# shelves_v60.net
KiCad netlist of a schematic drawn in EAGLE
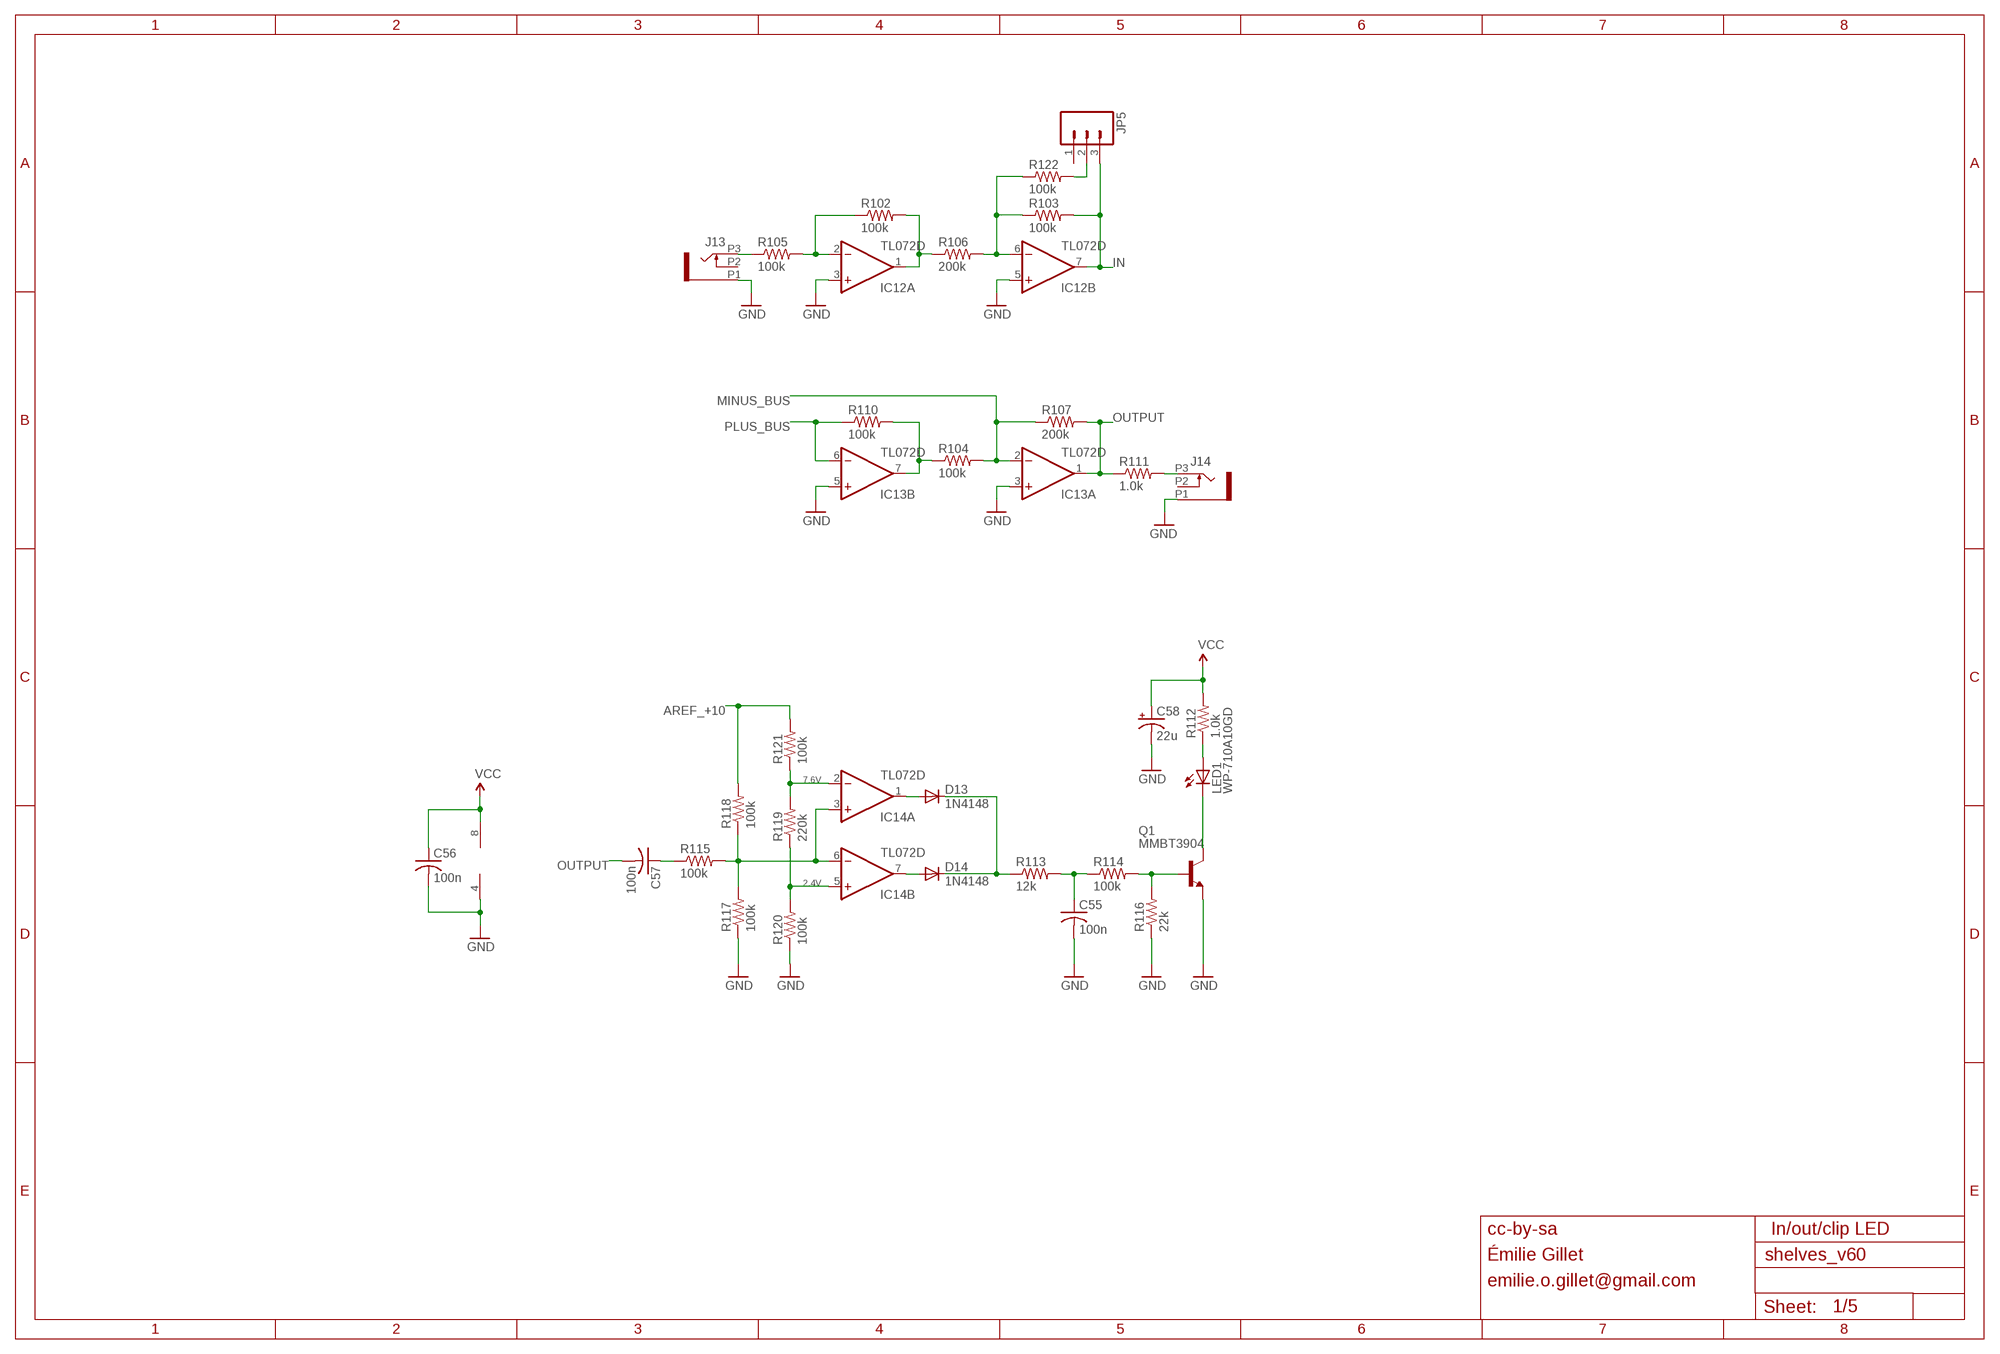
[diagram p0: schematic, sheet 1]
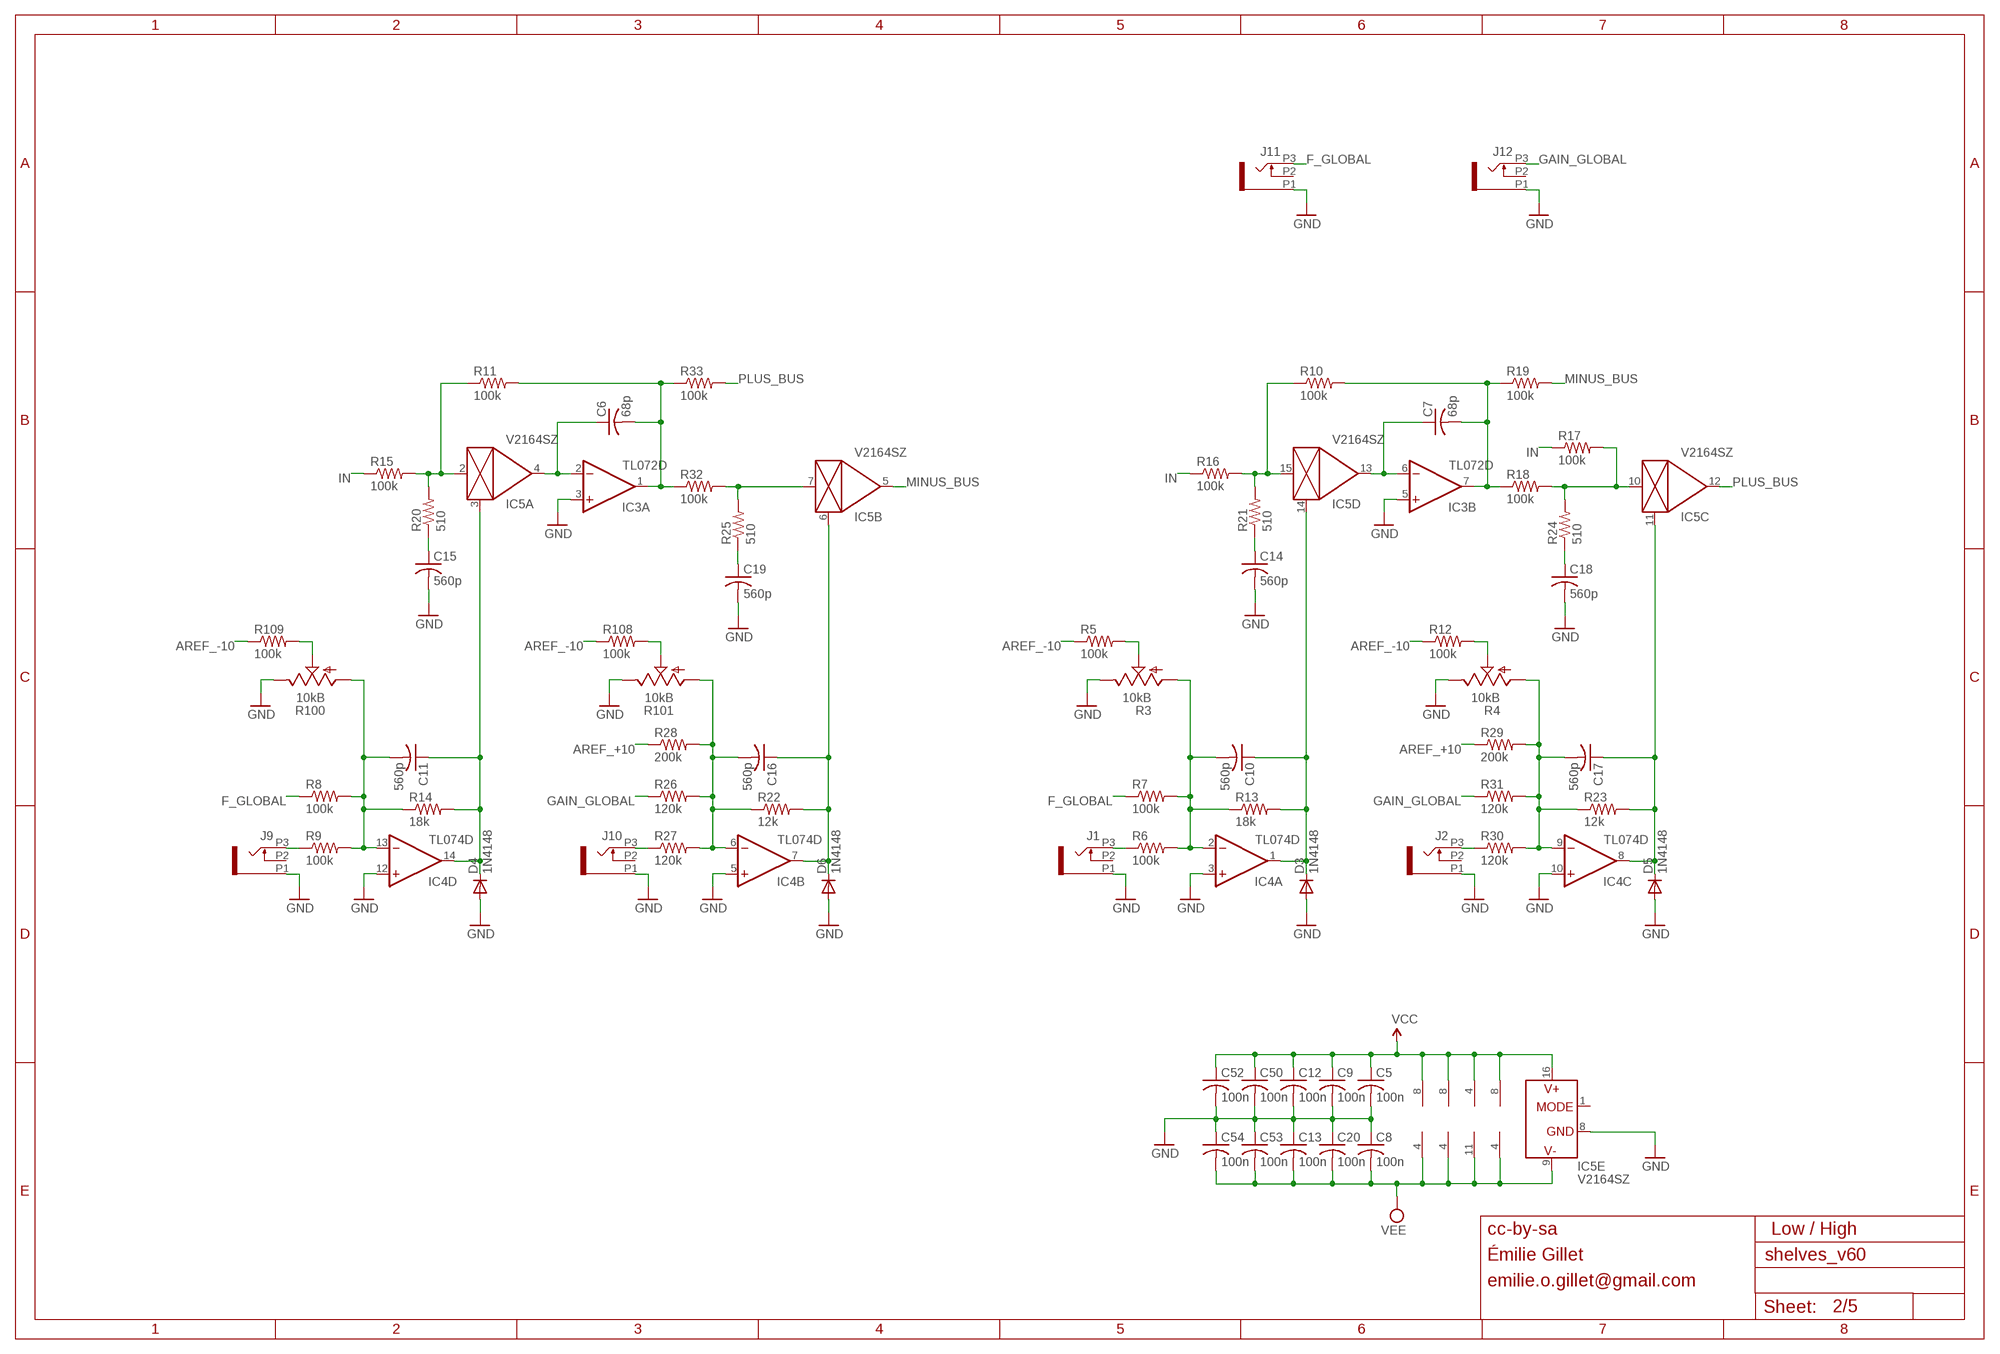
[diagram p1: schematic, sheet 2]
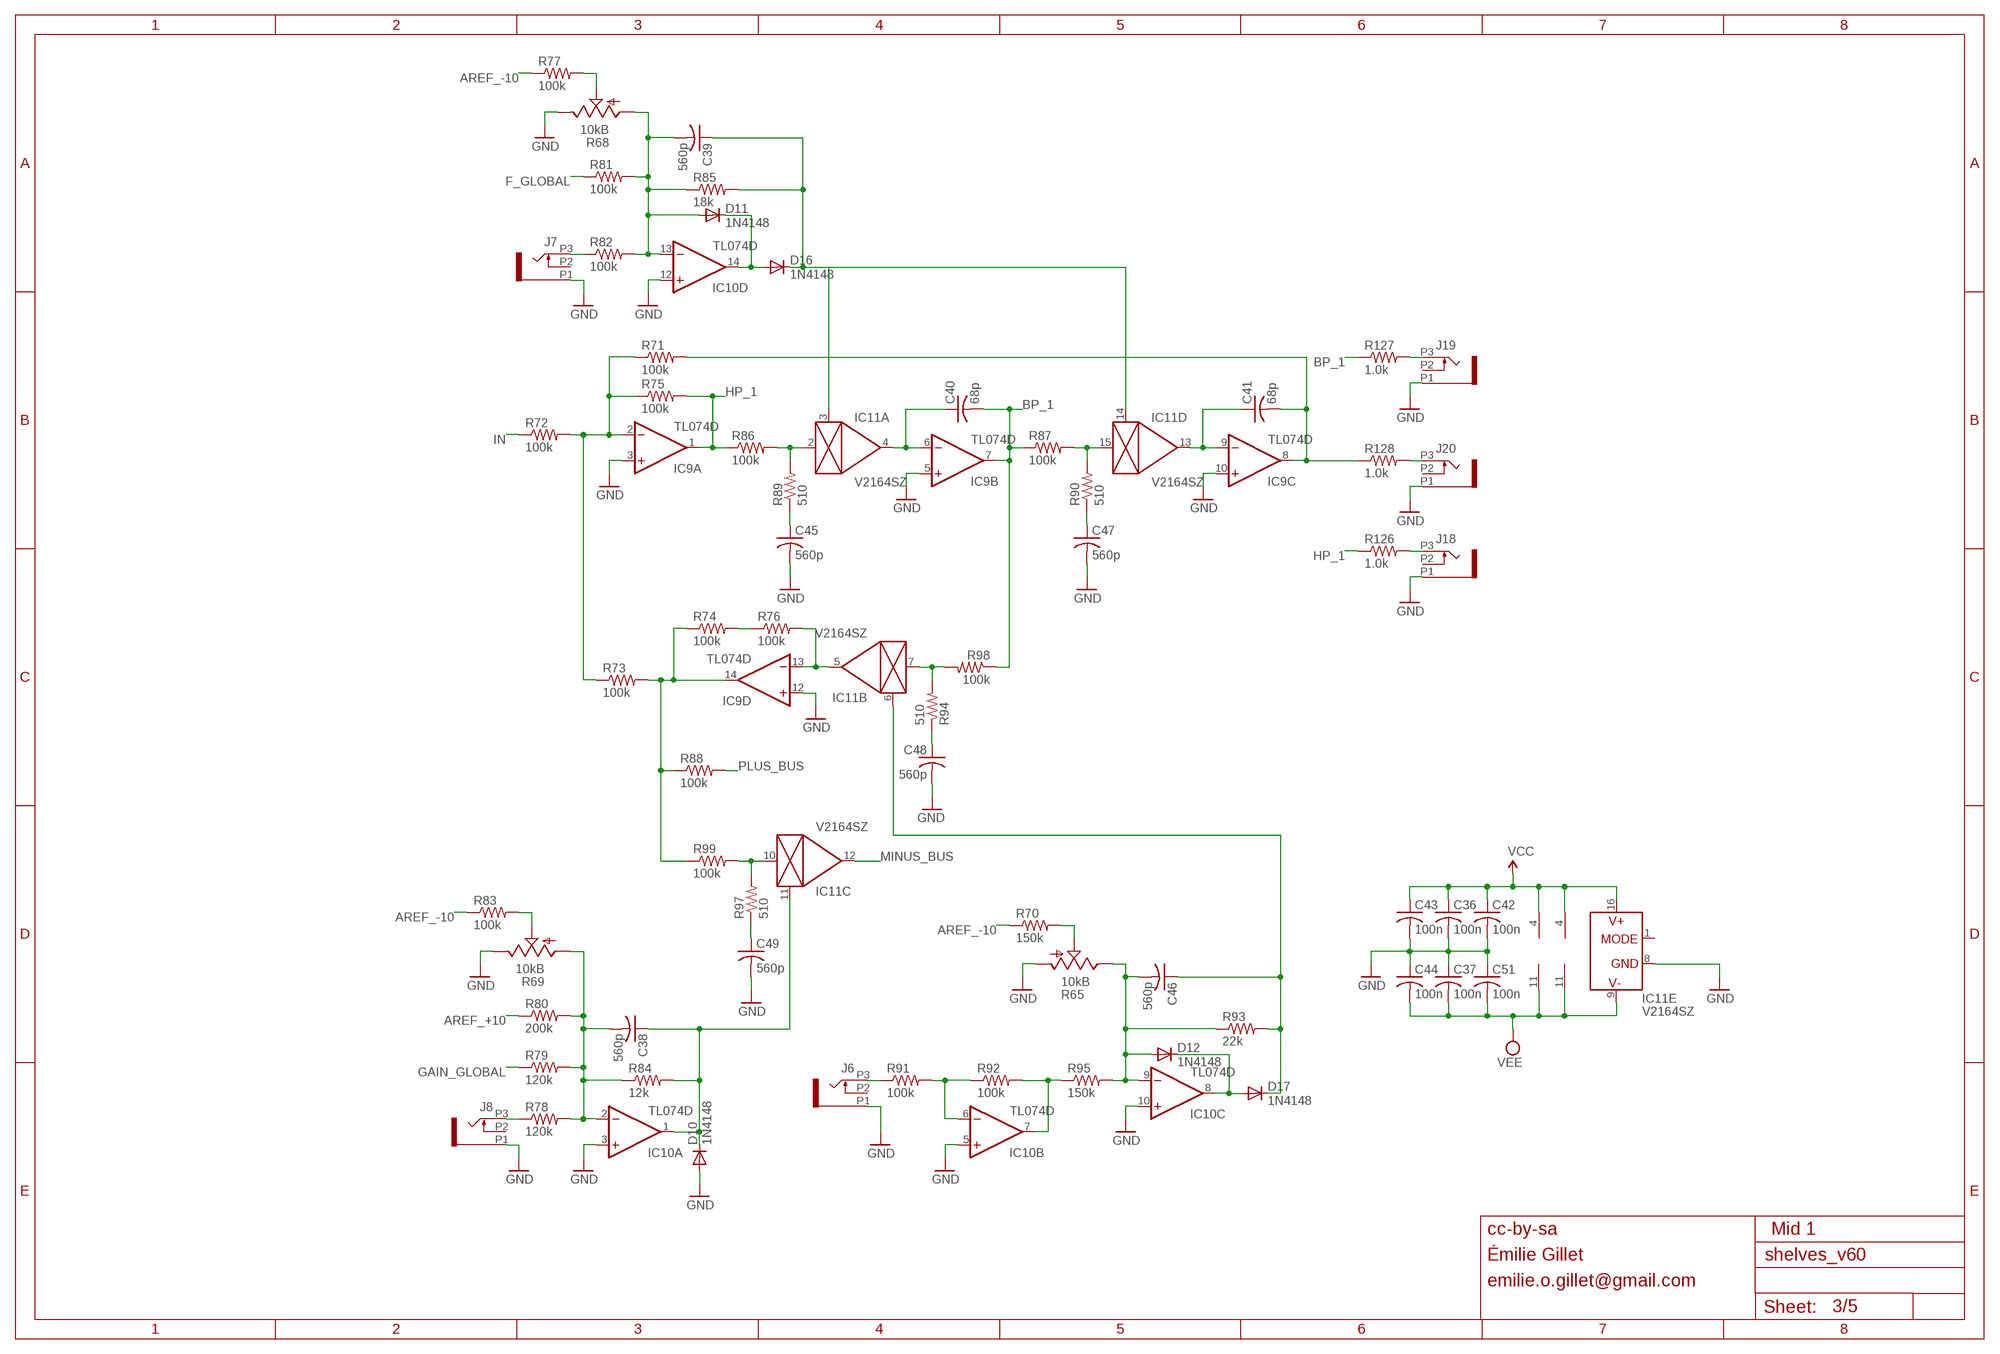
[diagram p2: schematic, sheet 3]
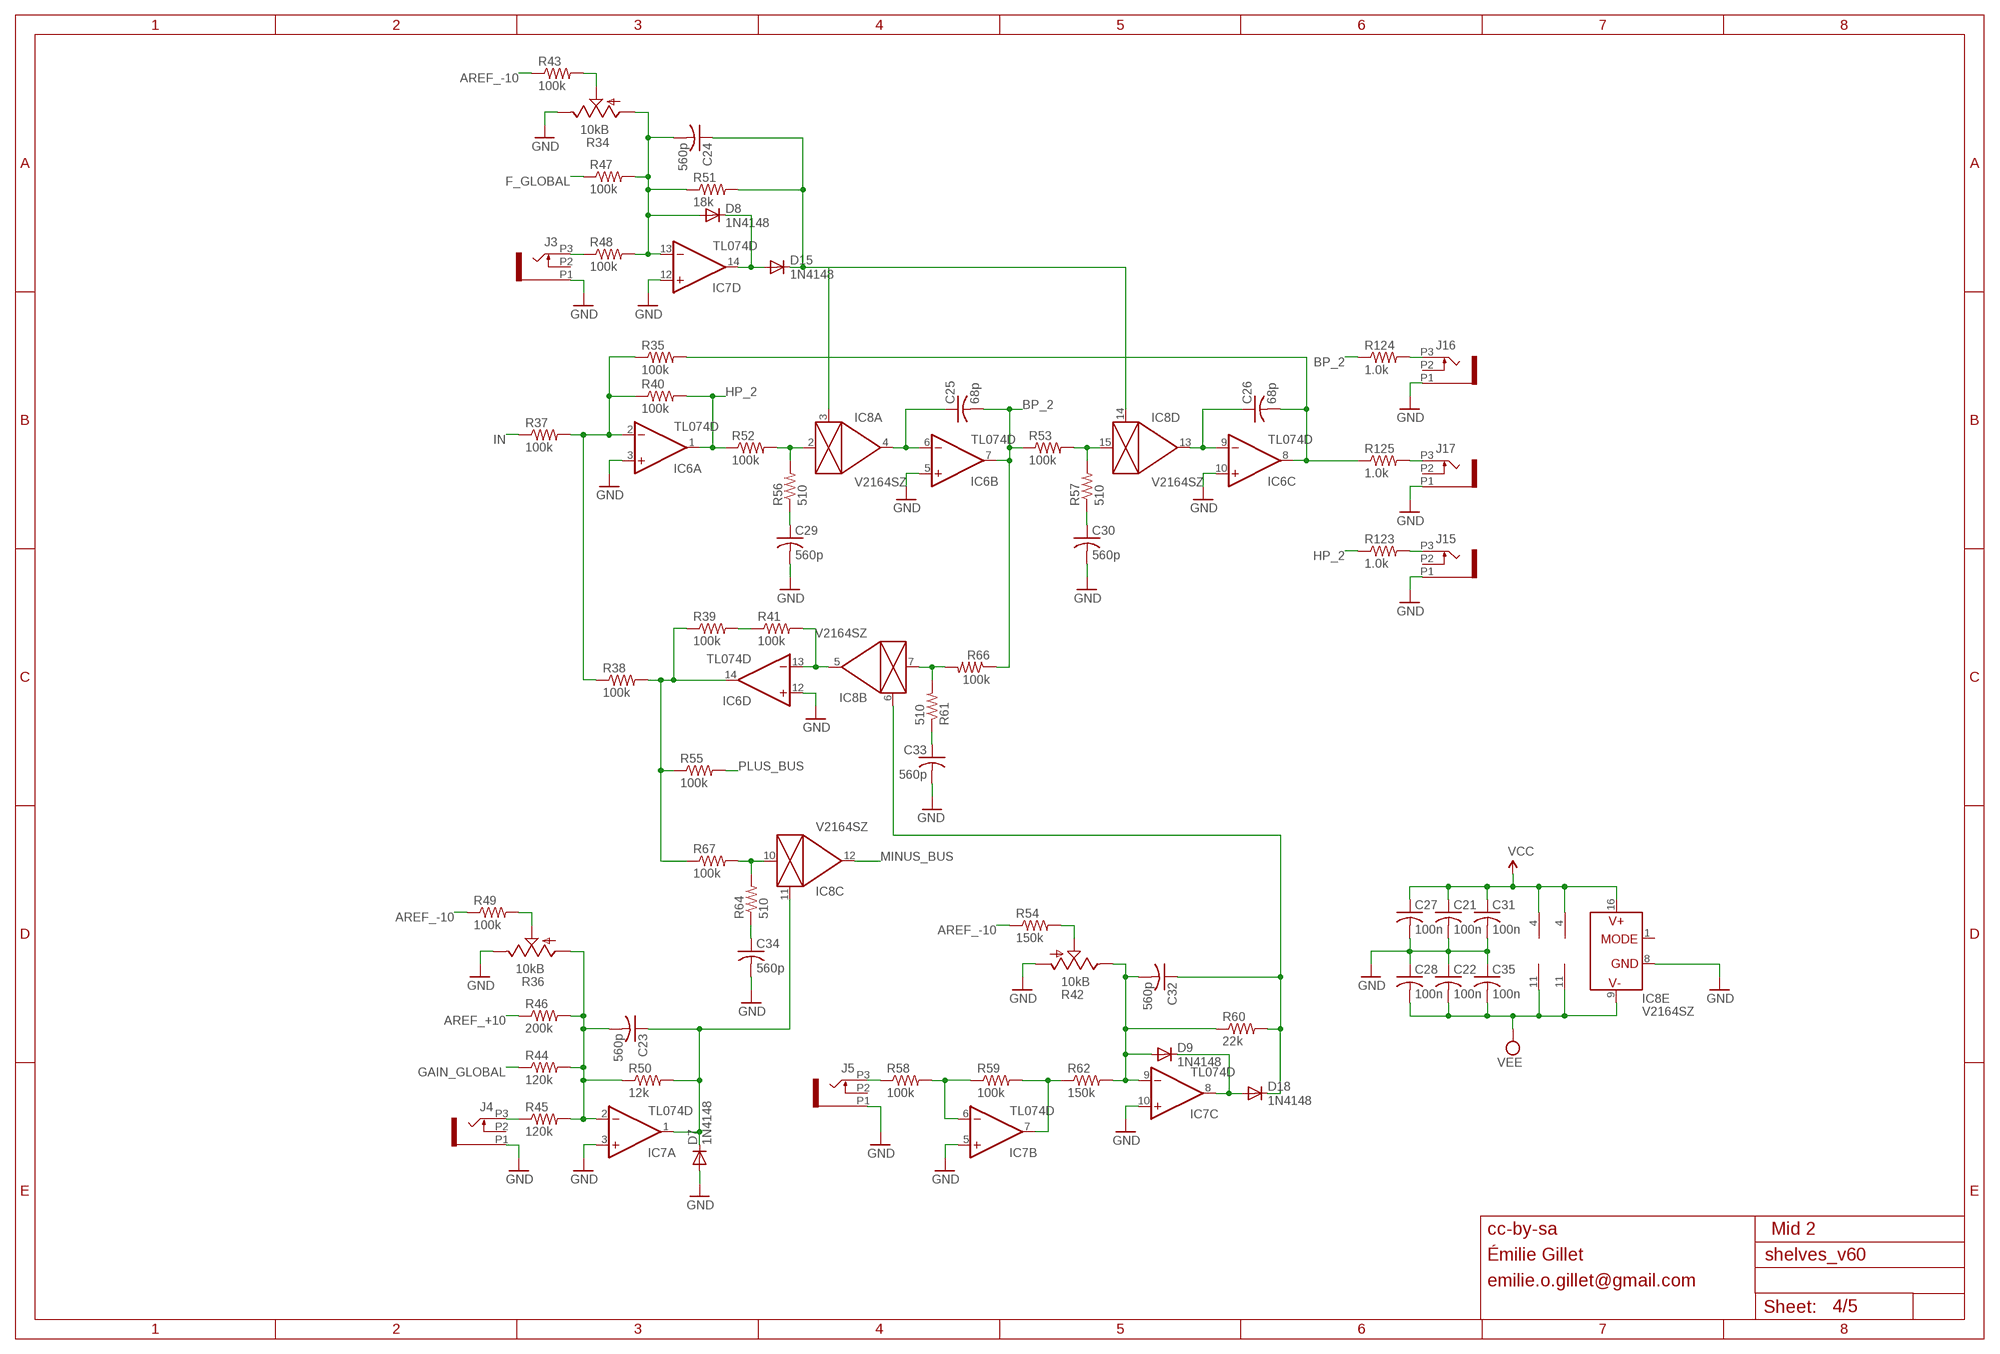
[diagram p3: schematic, sheet 4]
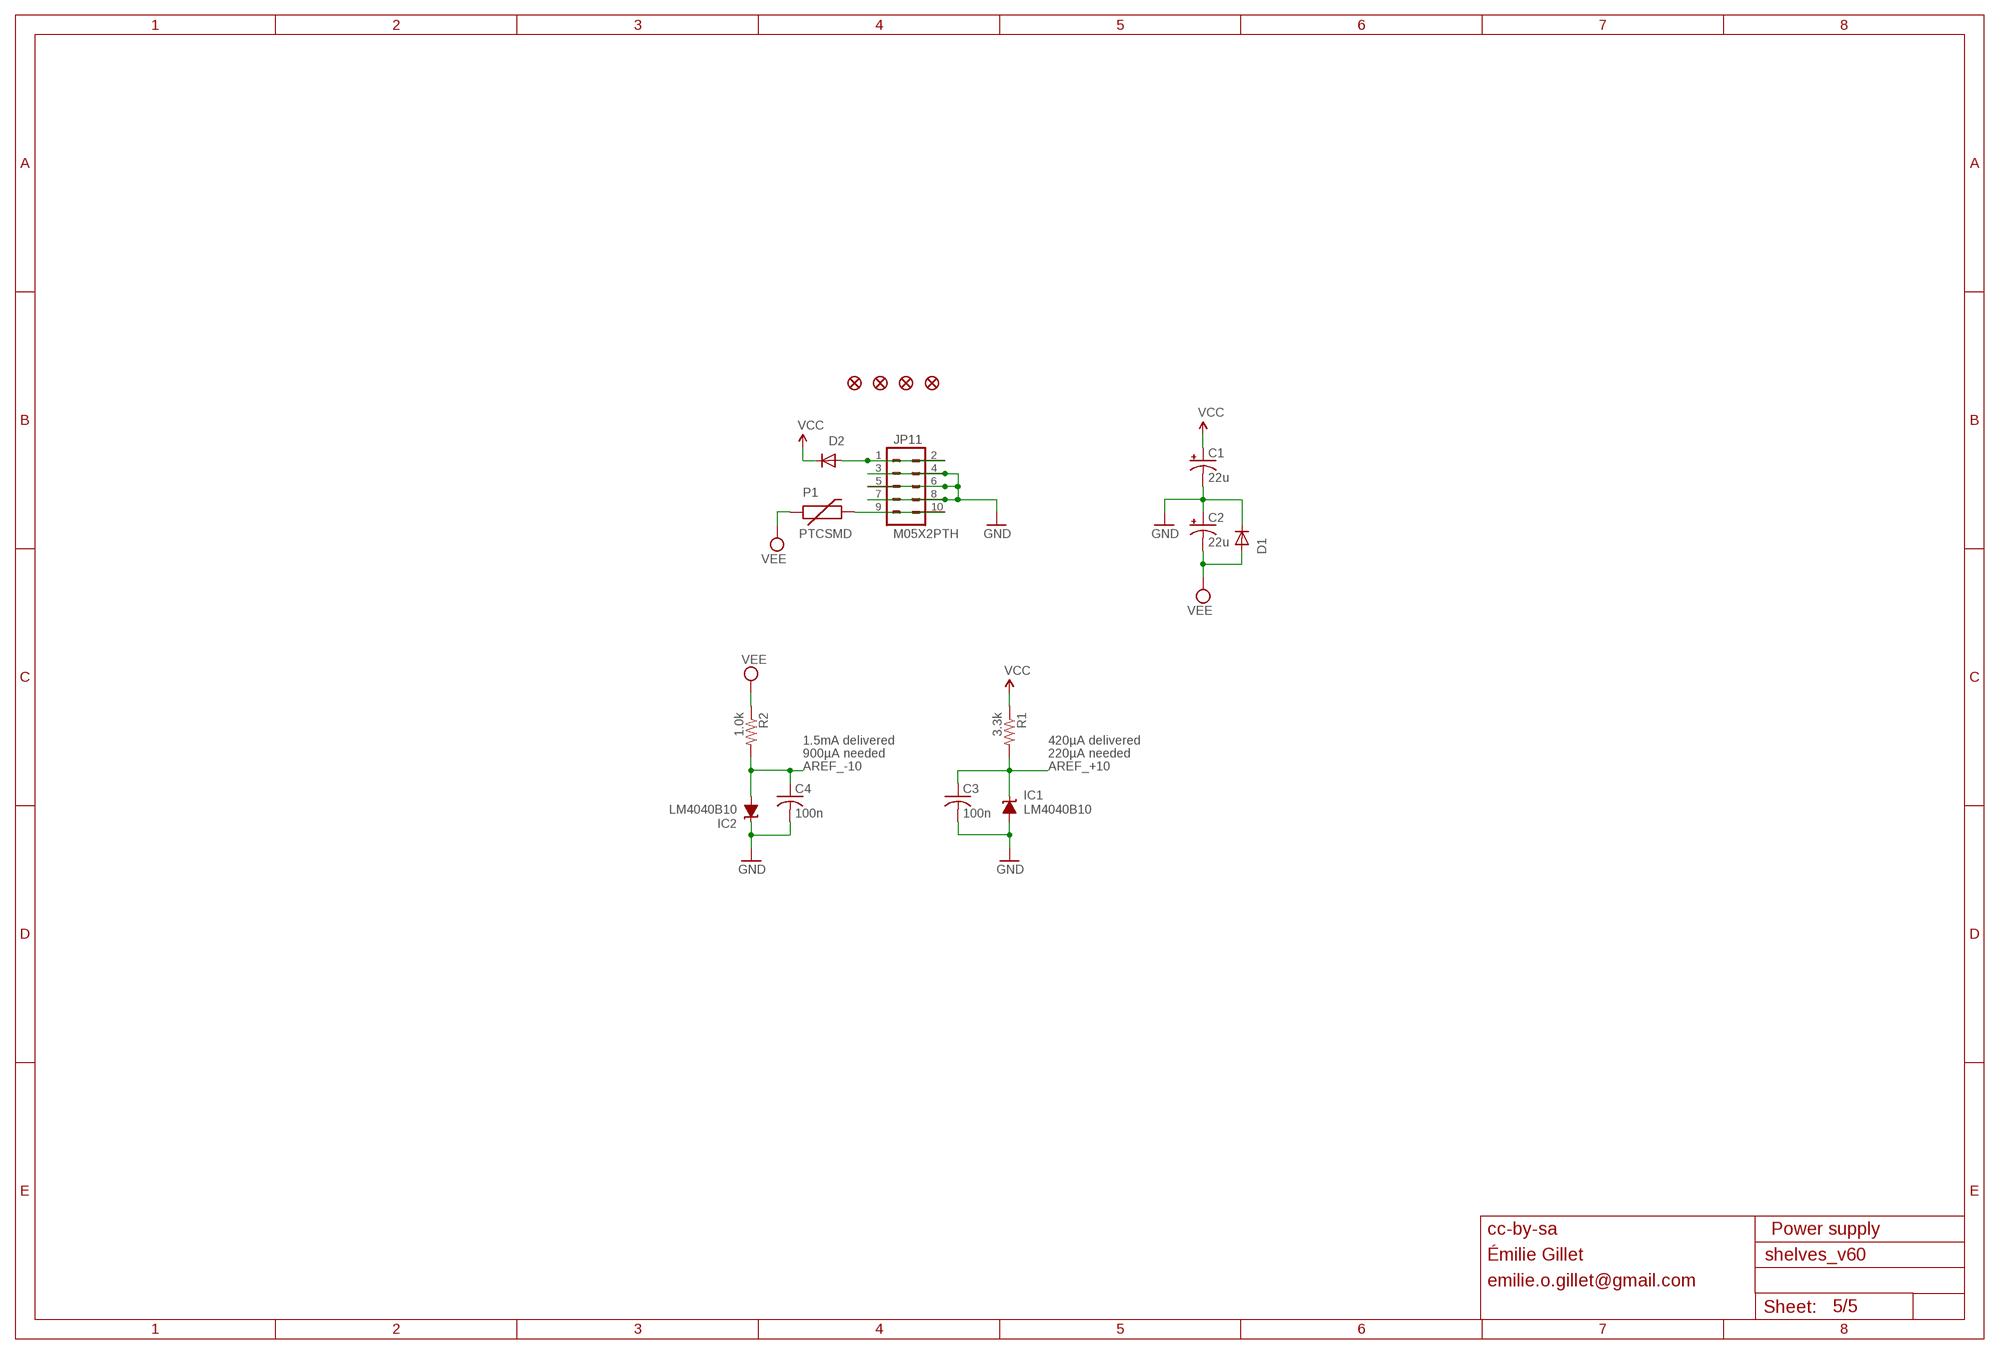
[diagram p4: schematic, sheet 5]

(export (version "E")
  (design (tool "Eeschema 10.0.6"))
  (components
    (comp (ref "C21")
      (value "100n")
      (footprint "eagle-import:C0603")
      (libsource (lib "eagle-import") (part "C-USC0603"))
    )
    (comp (ref "C22")
      (value "100n")
      (footprint "eagle-import:C0603")
      (libsource (lib "eagle-import") (part "C-USC0603"))
    )
    (comp (ref "C23")
      (value "560p")
      (footprint "eagle-import:C0603")
      (libsource (lib "eagle-import") (part "C-USC0603"))
    )
    (comp (ref "C24")
      (value "560p")
      (footprint "eagle-import:C0603")
      (libsource (lib "eagle-import") (part "C-USC0603"))
    )
    (comp (ref "C25")
      (value "68p")
      (footprint "eagle-import:C0603")
      (libsource (lib "eagle-import") (part "C-USC0603"))
    )
    (comp (ref "C26")
      (value "68p")
      (footprint "eagle-import:C0603")
      (libsource (lib "eagle-import") (part "C-USC0603"))
    )
    (comp (ref "C27")
      (value "100n")
      (footprint "eagle-import:C0603")
      (libsource (lib "eagle-import") (part "C-USC0603"))
    )
    (comp (ref "C28")
      (value "100n")
      (footprint "eagle-import:C0603")
      (libsource (lib "eagle-import") (part "C-USC0603"))
    )
    (comp (ref "C29")
      (value "560p")
      (footprint "eagle-import:C0603")
      (libsource (lib "eagle-import") (part "C-USC0603"))
    )
    (comp (ref "C30")
      (value "560p")
      (footprint "eagle-import:C0603")
      (libsource (lib "eagle-import") (part "C-USC0603"))
    )
    (comp (ref "C31")
      (value "100n")
      (footprint "eagle-import:C0603")
      (libsource (lib "eagle-import") (part "C-USC0603"))
    )
    (comp (ref "C32")
      (value "560p")
      (footprint "eagle-import:C0603")
      (libsource (lib "eagle-import") (part "C-USC0603"))
    )
    (comp (ref "C33")
      (value "560p")
      (footprint "eagle-import:C0603")
      (libsource (lib "eagle-import") (part "C-USC0603"))
    )
    (comp (ref "C34")
      (value "560p")
      (footprint "eagle-import:C0603")
      (libsource (lib "eagle-import") (part "C-USC0603"))
    )
    (comp (ref "C35")
      (value "100n")
      (footprint "eagle-import:C0603")
      (libsource (lib "eagle-import") (part "C-USC0603"))
    )
    (comp (ref "D7")
      (value "1N4148")
      (footprint "eagle-import:SOD323-W")
      (libsource (lib "eagle-import") (part "DIODE-SOD323-W"))
    )
    (comp (ref "D8")
      (value "1N4148")
      (footprint "eagle-import:SOD323-W")
      (libsource (lib "eagle-import") (part "DIODE-SOD323-W"))
    )
    (comp (ref "D9")
      (value "1N4148")
      (footprint "eagle-import:SOD323-W")
      (libsource (lib "eagle-import") (part "DIODE-SOD323-W"))
    )
    (comp (ref "D15")
      (value "1N4148")
      (footprint "eagle-import:SOD323-W")
      (libsource (lib "eagle-import") (part "DIODE-SOD323-W"))
    )
    (comp (ref "D18")
      (value "1N4148")
      (footprint "eagle-import:SOD323-W")
      (libsource (lib "eagle-import") (part "DIODE-SOD323-W"))
    )
    (comp (ref "IC6")
      (value "TL074D")
      (footprint "eagle-import:SO14")
      (libsource (lib "eagle-import") (part "TL074D"))
    )
    (comp (ref "IC7")
      (value "TL074D")
      (footprint "eagle-import:SO14")
      (libsource (lib "eagle-import") (part "TL074D"))
    )
    (comp (ref "IC8")
      (value "V2164SZ")
      (footprint "eagle-import:SOIC16N")
      (libsource (lib "eagle-import") (part "SSM2164S"))
    )
    (comp (ref "J3")
      (value "PJ301_THONKICONN6")
      (footprint "eagle-import:WQP_PJ_301M6")
      (libsource (lib "eagle-import") (part "PJ301_THONKICONN6"))
    )
    (comp (ref "J4")
      (value "PJ301_THONKICONN6")
      (footprint "eagle-import:WQP_PJ_301M6")
      (libsource (lib "eagle-import") (part "PJ301_THONKICONN6"))
    )
    (comp (ref "J5")
      (value "PJ301_THONKICONN6")
      (footprint "eagle-import:WQP_PJ_301M6")
      (libsource (lib "eagle-import") (part "PJ301_THONKICONN6"))
    )
    (comp (ref "J15")
      (value "PJ301_THONKICONN6")
      (footprint "eagle-import:WQP_PJ_301M6")
      (libsource (lib "eagle-import") (part "PJ301_THONKICONN6"))
    )
    (comp (ref "J16")
      (value "PJ301_THONKICONN6")
      (footprint "eagle-import:WQP_PJ_301M6")
      (libsource (lib "eagle-import") (part "PJ301_THONKICONN6"))
    )
    (comp (ref "J17")
      (value "PJ301_THONKICONN6")
      (footprint "eagle-import:WQP_PJ_301M6")
      (libsource (lib "eagle-import") (part "PJ301_THONKICONN6"))
    )
    (comp (ref "R34")
      (value "10kB")
      (footprint "eagle-import:ALPS_POT_VERTICAL_PS")
      (libsource (lib "eagle-import") (part "POT_USVERTICAL_PS"))
    )
    (comp (ref "R35")
      (value "100k")
      (footprint "eagle-import:R0603")
      (libsource (lib "eagle-import") (part "R-US_R0603"))
    )
    (comp (ref "R36")
      (value "10kB")
      (footprint "eagle-import:ALPS_POT_VERTICAL_PS")
      (libsource (lib "eagle-import") (part "POT_USVERTICAL_PS"))
    )
    (comp (ref "R37")
      (value "100k")
      (footprint "eagle-import:R0603")
      (libsource (lib "eagle-import") (part "R-US_R0603"))
    )
    (comp (ref "R38")
      (value "100k")
      (footprint "eagle-import:R0603")
      (libsource (lib "eagle-import") (part "R-US_R0603"))
    )
    (comp (ref "R39")
      (value "100k")
      (footprint "eagle-import:R0603")
      (libsource (lib "eagle-import") (part "R-US_R0603"))
    )
    (comp (ref "R40")
      (value "100k")
      (footprint "eagle-import:R0603")
      (libsource (lib "eagle-import") (part "R-US_R0603"))
    )
    (comp (ref "R41")
      (value "100k")
      (footprint "eagle-import:R0603")
      (libsource (lib "eagle-import") (part "R-US_R0603"))
    )
    (comp (ref "R42")
      (value "10kB")
      (footprint "eagle-import:ALPS_POT_VERTICAL")
      (libsource (lib "eagle-import") (part "POT_USVERTICAL"))
    )
    (comp (ref "R43")
      (value "100k")
      (footprint "eagle-import:R0603")
      (libsource (lib "eagle-import") (part "R-US_R0603"))
    )
    (comp (ref "R44")
      (value "120k")
      (footprint "eagle-import:R0603")
      (libsource (lib "eagle-import") (part "R-US_R0603"))
    )
    (comp (ref "R45")
      (value "120k")
      (footprint "eagle-import:R0603")
      (libsource (lib "eagle-import") (part "R-US_R0603"))
    )
    (comp (ref "R46")
      (value "200k")
      (footprint "eagle-import:R0603")
      (libsource (lib "eagle-import") (part "R-US_R0603"))
    )
    (comp (ref "R47")
      (value "100k")
      (footprint "eagle-import:R0603")
      (libsource (lib "eagle-import") (part "R-US_R0603"))
    )
    (comp (ref "R48")
      (value "100k")
      (footprint "eagle-import:R0603")
      (libsource (lib "eagle-import") (part "R-US_R0603"))
    )
    (comp (ref "R49")
      (value "100k")
      (footprint "eagle-import:R0603")
      (libsource (lib "eagle-import") (part "R-US_R0603"))
    )
    (comp (ref "R50")
      (value "12k")
      (footprint "eagle-import:R0603")
      (libsource (lib "eagle-import") (part "R-US_R0603"))
    )
    (comp (ref "R51")
      (value "18k")
      (footprint "eagle-import:R0603")
      (libsource (lib "eagle-import") (part "R-US_R0603"))
    )
    (comp (ref "R52")
      (value "100k")
      (footprint "eagle-import:R0603")
      (libsource (lib "eagle-import") (part "R-US_R0603"))
    )
    (comp (ref "R53")
      (value "100k")
      (footprint "eagle-import:R0603")
      (libsource (lib "eagle-import") (part "R-US_R0603"))
    )
    (comp (ref "R54")
      (value "150k")
      (footprint "eagle-import:R0603")
      (libsource (lib "eagle-import") (part "R-US_R0603"))
    )
    (comp (ref "R55")
      (value "100k")
      (footprint "eagle-import:R0603")
      (libsource (lib "eagle-import") (part "R-US_R0603"))
    )
    (comp (ref "R56")
      (value "510")
      (footprint "eagle-import:R0603")
      (libsource (lib "eagle-import") (part "R-US_R0603"))
    )
    (comp (ref "R57")
      (value "510")
      (footprint "eagle-import:R0603")
      (libsource (lib "eagle-import") (part "R-US_R0603"))
    )
    (comp (ref "R58")
      (value "100k")
      (footprint "eagle-import:R0603")
      (libsource (lib "eagle-import") (part "R-US_R0603"))
    )
    (comp (ref "R59")
      (value "100k")
      (footprint "eagle-import:R0603")
      (libsource (lib "eagle-import") (part "R-US_R0603"))
    )
    (comp (ref "R60")
      (value "22k")
      (footprint "eagle-import:R0603")
      (libsource (lib "eagle-import") (part "R-US_R0603"))
    )
    (comp (ref "R61")
      (value "510")
      (footprint "eagle-import:R0603")
      (libsource (lib "eagle-import") (part "R-US_R0603"))
    )
    (comp (ref "R62")
      (value "150k")
      (footprint "eagle-import:R0603")
      (libsource (lib "eagle-import") (part "R-US_R0603"))
    )
    (comp (ref "R64")
      (value "510")
      (footprint "eagle-import:R0603")
      (libsource (lib "eagle-import") (part "R-US_R0603"))
    )
    (comp (ref "R66")
      (value "100k")
      (footprint "eagle-import:R0603")
      (libsource (lib "eagle-import") (part "R-US_R0603"))
    )
    (comp (ref "R67")
      (value "100k")
      (footprint "eagle-import:R0603")
      (libsource (lib "eagle-import") (part "R-US_R0603"))
    )
    (comp (ref "R123")
      (value "1.0k")
      (footprint "eagle-import:R0603")
      (libsource (lib "eagle-import") (part "R-US_R0603"))
    )
    (comp (ref "R124")
      (value "1.0k")
      (footprint "eagle-import:R0603")
      (libsource (lib "eagle-import") (part "R-US_R0603"))
    )
    (comp (ref "R125")
      (value "1.0k")
      (footprint "eagle-import:R0603")
      (libsource (lib "eagle-import") (part "R-US_R0603"))
    )
    (comp (ref "C5")
      (value "100n")
      (footprint "eagle-import:C0603")
      (libsource (lib "eagle-import") (part "C-USC0603"))
    )
    (comp (ref "C6")
      (value "68p")
      (footprint "eagle-import:C0603")
      (libsource (lib "eagle-import") (part "C-USC0603"))
    )
    (comp (ref "C7")
      (value "68p")
      (footprint "eagle-import:C0603")
      (libsource (lib "eagle-import") (part "C-USC0603"))
    )
    (comp (ref "C8")
      (value "100n")
      (footprint "eagle-import:C0603")
      (libsource (lib "eagle-import") (part "C-USC0603"))
    )
    (comp (ref "C9")
      (value "100n")
      (footprint "eagle-import:C0603")
      (libsource (lib "eagle-import") (part "C-USC0603"))
    )
    (comp (ref "C10")
      (value "560p")
      (footprint "eagle-import:C0603")
      (libsource (lib "eagle-import") (part "C-USC0603"))
    )
    (comp (ref "C11")
      (value "560p")
      (footprint "eagle-import:C0603")
      (libsource (lib "eagle-import") (part "C-USC0603"))
    )
    (comp (ref "C12")
      (value "100n")
      (footprint "eagle-import:C0603")
      (libsource (lib "eagle-import") (part "C-USC0603"))
    )
    (comp (ref "C13")
      (value "100n")
      (footprint "eagle-import:C0603")
      (libsource (lib "eagle-import") (part "C-USC0603"))
    )
    (comp (ref "C14")
      (value "560p")
      (footprint "eagle-import:C0603")
      (libsource (lib "eagle-import") (part "C-USC0603"))
    )
    (comp (ref "C15")
      (value "560p")
      (footprint "eagle-import:C0603")
      (libsource (lib "eagle-import") (part "C-USC0603"))
    )
    (comp (ref "C16")
      (value "560p")
      (footprint "eagle-import:C0603")
      (libsource (lib "eagle-import") (part "C-USC0603"))
    )
    (comp (ref "C17")
      (value "560p")
      (footprint "eagle-import:C0603")
      (libsource (lib "eagle-import") (part "C-USC0603"))
    )
    (comp (ref "C18")
      (value "560p")
      (footprint "eagle-import:C0603")
      (libsource (lib "eagle-import") (part "C-USC0603"))
    )
    (comp (ref "C19")
      (value "560p")
      (footprint "eagle-import:C0603")
      (libsource (lib "eagle-import") (part "C-USC0603"))
    )
    (comp (ref "C20")
      (value "100n")
      (footprint "eagle-import:C0603")
      (libsource (lib "eagle-import") (part "C-USC0603"))
    )
    (comp (ref "C50")
      (value "100n")
      (footprint "eagle-import:C0603")
      (libsource (lib "eagle-import") (part "C-USC0603"))
    )
    (comp (ref "C52")
      (value "100n")
      (footprint "eagle-import:C0603")
      (libsource (lib "eagle-import") (part "C-USC0603"))
    )
    (comp (ref "C53")
      (value "100n")
      (footprint "eagle-import:C0603")
      (libsource (lib "eagle-import") (part "C-USC0603"))
    )
    (comp (ref "C54")
      (value "100n")
      (footprint "eagle-import:C0603")
      (libsource (lib "eagle-import") (part "C-USC0603"))
    )
    (comp (ref "D3")
      (value "1N4148")
      (footprint "eagle-import:SOD323-W")
      (libsource (lib "eagle-import") (part "DIODE-SOD323-W"))
    )
    (comp (ref "D4")
      (value "1N4148")
      (footprint "eagle-import:SOD323-W")
      (libsource (lib "eagle-import") (part "DIODE-SOD323-W"))
    )
    (comp (ref "D5")
      (value "1N4148")
      (footprint "eagle-import:SOD323-W")
      (libsource (lib "eagle-import") (part "DIODE-SOD323-W"))
    )
    (comp (ref "D6")
      (value "1N4148")
      (footprint "eagle-import:SOD323-W")
      (libsource (lib "eagle-import") (part "DIODE-SOD323-W"))
    )
    (comp (ref "IC3")
      (value "TL072D")
      (footprint "eagle-import:SO08")
      (libsource (lib "eagle-import") (part "TL072D"))
    )
    (comp (ref "IC4")
      (value "TL074D")
      (footprint "eagle-import:SO14")
      (libsource (lib "eagle-import") (part "TL074D"))
    )
    (comp (ref "IC5")
      (value "V2164SZ")
      (footprint "eagle-import:SOIC16N")
      (libsource (lib "eagle-import") (part "SSM2164S"))
    )
    (comp (ref "IC12")
      (value "TL072D")
      (footprint "eagle-import:SO08")
      (libsource (lib "eagle-import") (part "TL072D"))
    )
    (comp (ref "IC13")
      (value "TL072D")
      (footprint "eagle-import:SO08")
      (libsource (lib "eagle-import") (part "TL072D"))
    )
    (comp (ref "J1")
      (value "PJ301_THONKICONN6")
      (footprint "eagle-import:WQP_PJ_301M6")
      (libsource (lib "eagle-import") (part "PJ301_THONKICONN6"))
    )
    (comp (ref "J2")
      (value "PJ301_THONKICONN6")
      (footprint "eagle-import:WQP_PJ_301M6")
      (libsource (lib "eagle-import") (part "PJ301_THONKICONN6"))
    )
    (comp (ref "J9")
      (value "PJ301_THONKICONN6")
      (footprint "eagle-import:WQP_PJ_301M6")
      (libsource (lib "eagle-import") (part "PJ301_THONKICONN6"))
    )
    (comp (ref "J10")
      (value "PJ301_THONKICONN6")
      (footprint "eagle-import:WQP_PJ_301M6")
      (libsource (lib "eagle-import") (part "PJ301_THONKICONN6"))
    )
    (comp (ref "J11")
      (value "PJ301_THONKICONN6")
      (footprint "eagle-import:WQP_PJ_301M6")
      (libsource (lib "eagle-import") (part "PJ301_THONKICONN6"))
    )
    (comp (ref "J12")
      (value "PJ301_THONKICONN6")
      (footprint "eagle-import:WQP_PJ_301M6")
      (libsource (lib "eagle-import") (part "PJ301_THONKICONN6"))
    )
    (comp (ref "R3")
      (value "10kB")
      (footprint "eagle-import:ALPS_POT_VERTICAL_PS")
      (libsource (lib "eagle-import") (part "POT_USVERTICAL_PS"))
    )
    (comp (ref "R4")
      (value "10kB")
      (footprint "eagle-import:ALPS_POT_VERTICAL_PS")
      (libsource (lib "eagle-import") (part "POT_USVERTICAL_PS"))
    )
    (comp (ref "R5")
      (value "100k")
      (footprint "eagle-import:R0603")
      (libsource (lib "eagle-import") (part "R-US_R0603"))
    )
    (comp (ref "R6")
      (value "100k")
      (footprint "eagle-import:R0603")
      (libsource (lib "eagle-import") (part "R-US_R0603"))
    )
    (comp (ref "R7")
      (value "100k")
      (footprint "eagle-import:R0603")
      (libsource (lib "eagle-import") (part "R-US_R0603"))
    )
    (comp (ref "R8")
      (value "100k")
      (footprint "eagle-import:R0603")
      (libsource (lib "eagle-import") (part "R-US_R0603"))
    )
    (comp (ref "R9")
      (value "100k")
      (footprint "eagle-import:R0603")
      (libsource (lib "eagle-import") (part "R-US_R0603"))
    )
    (comp (ref "R10")
      (value "100k")
      (footprint "eagle-import:R0603")
      (libsource (lib "eagle-import") (part "R-US_R0603"))
    )
    (comp (ref "R11")
      (value "100k")
      (footprint "eagle-import:R0603")
      (libsource (lib "eagle-import") (part "R-US_R0603"))
    )
    (comp (ref "R12")
      (value "100k")
      (footprint "eagle-import:R0603")
      (libsource (lib "eagle-import") (part "R-US_R0603"))
    )
    (comp (ref "R13")
      (value "18k")
      (footprint "eagle-import:R0603")
      (libsource (lib "eagle-import") (part "R-US_R0603"))
    )
    (comp (ref "R14")
      (value "18k")
      (footprint "eagle-import:R0603")
      (libsource (lib "eagle-import") (part "R-US_R0603"))
    )
    (comp (ref "R15")
      (value "100k")
      (footprint "eagle-import:R0603")
      (libsource (lib "eagle-import") (part "R-US_R0603"))
    )
    (comp (ref "R16")
      (value "100k")
      (footprint "eagle-import:R0603")
      (libsource (lib "eagle-import") (part "R-US_R0603"))
    )
    (comp (ref "R17")
      (value "100k")
      (footprint "eagle-import:R0603")
      (libsource (lib "eagle-import") (part "R-US_R0603"))
    )
    (comp (ref "R18")
      (value "100k")
      (footprint "eagle-import:R0603")
      (libsource (lib "eagle-import") (part "R-US_R0603"))
    )
    (comp (ref "R19")
      (value "100k")
      (footprint "eagle-import:R0603")
      (libsource (lib "eagle-import") (part "R-US_R0603"))
    )
    (comp (ref "R20")
      (value "510")
      (footprint "eagle-import:R0603")
      (libsource (lib "eagle-import") (part "R-US_R0603"))
    )
    (comp (ref "R21")
      (value "510")
      (footprint "eagle-import:R0603")
      (libsource (lib "eagle-import") (part "R-US_R0603"))
    )
    (comp (ref "R22")
      (value "12k")
      (footprint "eagle-import:R0603")
      (libsource (lib "eagle-import") (part "R-US_R0603"))
    )
    (comp (ref "R23")
      (value "12k")
      (footprint "eagle-import:R0603")
      (libsource (lib "eagle-import") (part "R-US_R0603"))
    )
    (comp (ref "R24")
      (value "510")
      (footprint "eagle-import:R0603")
      (libsource (lib "eagle-import") (part "R-US_R0603"))
    )
    (comp (ref "R25")
      (value "510")
      (footprint "eagle-import:R0603")
      (libsource (lib "eagle-import") (part "R-US_R0603"))
    )
    (comp (ref "R26")
      (value "120k")
      (footprint "eagle-import:R0603")
      (libsource (lib "eagle-import") (part "R-US_R0603"))
    )
    (comp (ref "R27")
      (value "120k")
      (footprint "eagle-import:R0603")
      (libsource (lib "eagle-import") (part "R-US_R0603"))
    )
    (comp (ref "R28")
      (value "200k")
      (footprint "eagle-import:R0603")
      (libsource (lib "eagle-import") (part "R-US_R0603"))
    )
    (comp (ref "R29")
      (value "200k")
      (footprint "eagle-import:R0603")
      (libsource (lib "eagle-import") (part "R-US_R0603"))
    )
    (comp (ref "R30")
      (value "120k")
      (footprint "eagle-import:R0603")
      (libsource (lib "eagle-import") (part "R-US_R0603"))
    )
    (comp (ref "R31")
      (value "120k")
      (footprint "eagle-import:R0603")
      (libsource (lib "eagle-import") (part "R-US_R0603"))
    )
    (comp (ref "R32")
      (value "100k")
      (footprint "eagle-import:R0603")
      (libsource (lib "eagle-import") (part "R-US_R0603"))
    )
    (comp (ref "R33")
      (value "100k")
      (footprint "eagle-import:R0603")
      (libsource (lib "eagle-import") (part "R-US_R0603"))
    )
    (comp (ref "R100")
      (value "10kB")
      (footprint "eagle-import:ALPS_POT_VERTICAL_PS")
      (libsource (lib "eagle-import") (part "POT_USVERTICAL_PS"))
    )
    (comp (ref "R101")
      (value "10kB")
      (footprint "eagle-import:ALPS_POT_VERTICAL_PS")
      (libsource (lib "eagle-import") (part "POT_USVERTICAL_PS"))
    )
    (comp (ref "R108")
      (value "100k")
      (footprint "eagle-import:R0603")
      (libsource (lib "eagle-import") (part "R-US_R0603"))
    )
    (comp (ref "R109")
      (value "100k")
      (footprint "eagle-import:R0603")
      (libsource (lib "eagle-import") (part "R-US_R0603"))
    )
    (comp (ref "C55")
      (value "100n")
      (footprint "eagle-import:C0603")
      (libsource (lib "eagle-import") (part "C-USC0603"))
    )
    (comp (ref "C56")
      (value "100n")
      (footprint "eagle-import:C0603")
      (libsource (lib "eagle-import") (part "C-USC0603"))
    )
    (comp (ref "C57")
      (value "100n")
      (footprint "eagle-import:C0603")
      (libsource (lib "eagle-import") (part "C-USC0603"))
    )
    (comp (ref "C58")
      (value "22u")
      (footprint "eagle-import:PANASONIC_C")
      (libsource (lib "eagle-import") (part "CPOL-USC"))
    )
    (comp (ref "D13")
      (value "1N4148")
      (footprint "eagle-import:SOD323-W")
      (libsource (lib "eagle-import") (part "DIODE-SOD323-W"))
    )
    (comp (ref "D14")
      (value "1N4148")
      (footprint "eagle-import:SOD323-W")
      (libsource (lib "eagle-import") (part "DIODE-SOD323-W"))
    )
    (comp (ref "IC14")
      (value "TL072D")
      (footprint "eagle-import:SO08")
      (libsource (lib "eagle-import") (part "TL072D"))
    )
    (comp (ref "J13")
      (value "PJ301_THONKICONN6")
      (footprint "eagle-import:WQP_PJ_301M6")
      (libsource (lib "eagle-import") (part "PJ301_THONKICONN6"))
    )
    (comp (ref "J14")
      (value "PJ301_THONKICONN6")
      (footprint "eagle-import:WQP_PJ_301M6")
      (libsource (lib "eagle-import") (part "PJ301_THONKICONN6"))
    )
    (comp (ref "JP5")
      (value "M03PTH")
      (footprint "eagle-import:1X03")
      (libsource (lib "eagle-import") (part "M03PTH"))
    )
    (comp (ref "LED1")
      (value "WP-710A10GD")
      (footprint "eagle-import:LED3MM")
      (libsource (lib "eagle-import") (part "LED3MM"))
    )
    (comp (ref "Q1")
      (value "MMBT3904")
      (footprint "eagle-import:SOT23-BEC")
      (libsource (lib "eagle-import") (part "-NPN-SOT23-BECMMBT3904LT1"))
    )
    (comp (ref "R102")
      (value "100k")
      (footprint "eagle-import:R0603")
      (libsource (lib "eagle-import") (part "R-US_R0603"))
    )
    (comp (ref "R103")
      (value "100k")
      (footprint "eagle-import:R0603")
      (libsource (lib "eagle-import") (part "R-US_R0603"))
    )
    (comp (ref "R104")
      (value "100k")
      (footprint "eagle-import:R0603")
      (libsource (lib "eagle-import") (part "R-US_R0603"))
    )
    (comp (ref "R105")
      (value "100k")
      (footprint "eagle-import:R0603")
      (libsource (lib "eagle-import") (part "R-US_R0603"))
    )
    (comp (ref "R106")
      (value "200k")
      (footprint "eagle-import:R0603")
      (libsource (lib "eagle-import") (part "R-US_R0603"))
    )
    (comp (ref "R107")
      (value "200k")
      (footprint "eagle-import:R0603")
      (libsource (lib "eagle-import") (part "R-US_R0603"))
    )
    (comp (ref "R110")
      (value "100k")
      (footprint "eagle-import:R0603")
      (libsource (lib "eagle-import") (part "R-US_R0603"))
    )
    (comp (ref "R111")
      (value "1.0k")
      (footprint "eagle-import:R0603")
      (libsource (lib "eagle-import") (part "R-US_R0603"))
    )
    (comp (ref "R112")
      (value "1.0k")
      (footprint "eagle-import:R0603")
      (libsource (lib "eagle-import") (part "R-US_R0603"))
    )
    (comp (ref "R113")
      (value "12k")
      (footprint "eagle-import:R0603")
      (libsource (lib "eagle-import") (part "R-US_R0603"))
    )
    (comp (ref "R114")
      (value "100k")
      (footprint "eagle-import:R0603")
      (libsource (lib "eagle-import") (part "R-US_R0603"))
    )
    (comp (ref "R115")
      (value "100k")
      (footprint "eagle-import:R0603")
      (libsource (lib "eagle-import") (part "R-US_R0603"))
    )
    (comp (ref "R116")
      (value "22k")
      (footprint "eagle-import:R0603")
      (libsource (lib "eagle-import") (part "R-US_R0603"))
    )
    (comp (ref "R117")
      (value "100k")
      (footprint "eagle-import:R0603")
      (libsource (lib "eagle-import") (part "R-US_R0603"))
    )
    (comp (ref "R118")
      (value "100k")
      (footprint "eagle-import:R0603")
      (libsource (lib "eagle-import") (part "R-US_R0603"))
    )
    (comp (ref "R119")
      (value "220k")
      (footprint "eagle-import:R0603")
      (libsource (lib "eagle-import") (part "R-US_R0603"))
    )
    (comp (ref "R120")
      (value "100k")
      (footprint "eagle-import:R0603")
      (libsource (lib "eagle-import") (part "R-US_R0603"))
    )
    (comp (ref "R121")
      (value "100k")
      (footprint "eagle-import:R0603")
      (libsource (lib "eagle-import") (part "R-US_R0603"))
    )
    (comp (ref "R122")
      (value "100k")
      (footprint "eagle-import:R0603")
      (libsource (lib "eagle-import") (part "R-US_R0603"))
    )
    (comp (ref "C1")
      (value "22u")
      (footprint "eagle-import:PANASONIC_C")
      (libsource (lib "eagle-import") (part "CPOL-USC"))
    )
    (comp (ref "C2")
      (value "22u")
      (footprint "eagle-import:PANASONIC_C")
      (libsource (lib "eagle-import") (part "CPOL-USC"))
    )
    (comp (ref "C3")
      (value "100n")
      (footprint "eagle-import:C0603")
      (libsource (lib "eagle-import") (part "C-USC0603"))
    )
    (comp (ref "C4")
      (value "100n")
      (footprint "eagle-import:C0603")
      (libsource (lib "eagle-import") (part "C-USC0603"))
    )
    (comp (ref "D1")
      (value "1N5819HW")
      (footprint "eagle-import:SOD123")
      (libsource (lib "eagle-import") (part "DIODE-SOD123"))
    )
    (comp (ref "D2")
      (value "1N5819HW")
      (footprint "eagle-import:SOD123")
      (libsource (lib "eagle-import") (part "DIODE-SOD123"))
    )
    (comp (ref "IC1")
      (value "LM4040B10")
      (footprint "eagle-import:DBZ_R-PDSO-G3")
      (libsource (lib "eagle-import") (part "LM4041DBZB12"))
    )
    (comp (ref "IC2")
      (value "LM4040B10")
      (footprint "eagle-import:DBZ_R-PDSO-G3")
      (libsource (lib "eagle-import") (part "LM4041DBZB12"))
    )
    (comp (ref "JP1")
      (value "FIDUCIAL1X2")
      (footprint "eagle-import:FIDUCIAL-1X2")
      (libsource (lib "eagle-import") (part "FIDUCIAL1X2"))
    )
    (comp (ref "JP2")
      (value "FIDUCIAL1X2")
      (footprint "eagle-import:FIDUCIAL-1X2")
      (libsource (lib "eagle-import") (part "FIDUCIAL1X2"))
    )
    (comp (ref "JP3")
      (value "FIDUCIAL1X2")
      (footprint "eagle-import:FIDUCIAL-1X2")
      (libsource (lib "eagle-import") (part "FIDUCIAL1X2"))
    )
    (comp (ref "JP4")
      (value "FIDUCIAL1X2")
      (footprint "eagle-import:FIDUCIAL-1X2")
      (libsource (lib "eagle-import") (part "FIDUCIAL1X2"))
    )
    (comp (ref "JP11")
      (value "M05X2PTH")
      (footprint "eagle-import:AVR_ICSP")
      (libsource (lib "eagle-import") (part "M05X2PTH"))
    )
    (comp (ref "P1")
      (value "PTCSMD")
      (footprint "eagle-import:PTC-1206")
      (libsource (lib "eagle-import") (part "PTCSMD"))
    )
    (comp (ref "R1")
      (value "3.3k")
      (footprint "eagle-import:R0603")
      (libsource (lib "eagle-import") (part "R-US_R0603"))
    )
    (comp (ref "R2")
      (value "1.0k")
      (footprint "eagle-import:R0603")
      (libsource (lib "eagle-import") (part "R-US_R0603"))
    )
    (comp (ref "C36")
      (value "100n")
      (footprint "eagle-import:C0603")
      (libsource (lib "eagle-import") (part "C-USC0603"))
    )
    (comp (ref "C37")
      (value "100n")
      (footprint "eagle-import:C0603")
      (libsource (lib "eagle-import") (part "C-USC0603"))
    )
    (comp (ref "C38")
      (value "560p")
      (footprint "eagle-import:C0603")
      (libsource (lib "eagle-import") (part "C-USC0603"))
    )
    (comp (ref "C39")
      (value "560p")
      (footprint "eagle-import:C0603")
      (libsource (lib "eagle-import") (part "C-USC0603"))
    )
    (comp (ref "C40")
      (value "68p")
      (footprint "eagle-import:C0603")
      (libsource (lib "eagle-import") (part "C-USC0603"))
    )
    (comp (ref "C41")
      (value "68p")
      (footprint "eagle-import:C0603")
      (libsource (lib "eagle-import") (part "C-USC0603"))
    )
    (comp (ref "C42")
      (value "100n")
      (footprint "eagle-import:C0603")
      (libsource (lib "eagle-import") (part "C-USC0603"))
    )
    (comp (ref "C43")
      (value "100n")
      (footprint "eagle-import:C0603")
      (libsource (lib "eagle-import") (part "C-USC0603"))
    )
    (comp (ref "C44")
      (value "100n")
      (footprint "eagle-import:C0603")
      (libsource (lib "eagle-import") (part "C-USC0603"))
    )
    (comp (ref "C45")
      (value "560p")
      (footprint "eagle-import:C0603")
      (libsource (lib "eagle-import") (part "C-USC0603"))
    )
    (comp (ref "C46")
      (value "560p")
      (footprint "eagle-import:C0603")
      (libsource (lib "eagle-import") (part "C-USC0603"))
    )
    (comp (ref "C47")
      (value "560p")
      (footprint "eagle-import:C0603")
      (libsource (lib "eagle-import") (part "C-USC0603"))
    )
    (comp (ref "C48")
      (value "560p")
      (footprint "eagle-import:C0603")
      (libsource (lib "eagle-import") (part "C-USC0603"))
    )
    (comp (ref "C49")
      (value "560p")
      (footprint "eagle-import:C0603")
      (libsource (lib "eagle-import") (part "C-USC0603"))
    )
    (comp (ref "C51")
      (value "100n")
      (footprint "eagle-import:C0603")
      (libsource (lib "eagle-import") (part "C-USC0603"))
    )
    (comp (ref "D10")
      (value "1N4148")
      (footprint "eagle-import:SOD323-W")
      (libsource (lib "eagle-import") (part "DIODE-SOD323-W"))
    )
    (comp (ref "D11")
      (value "1N4148")
      (footprint "eagle-import:SOD323-W")
      (libsource (lib "eagle-import") (part "DIODE-SOD323-W"))
    )
    (comp (ref "D12")
      (value "1N4148")
      (footprint "eagle-import:SOD323-W")
      (libsource (lib "eagle-import") (part "DIODE-SOD323-W"))
    )
    (comp (ref "D16")
      (value "1N4148")
      (footprint "eagle-import:SOD323-W")
      (libsource (lib "eagle-import") (part "DIODE-SOD323-W"))
    )
    (comp (ref "D17")
      (value "1N4148")
      (footprint "eagle-import:SOD323-W")
      (libsource (lib "eagle-import") (part "DIODE-SOD323-W"))
    )
    (comp (ref "IC9")
      (value "TL074D")
      (footprint "eagle-import:SO14")
      (libsource (lib "eagle-import") (part "TL074D"))
    )
    (comp (ref "IC10")
      (value "TL074D")
      (footprint "eagle-import:SO14")
      (libsource (lib "eagle-import") (part "TL074D"))
    )
    (comp (ref "IC11")
      (value "V2164SZ")
      (footprint "eagle-import:SOIC16N")
      (libsource (lib "eagle-import") (part "SSM2164S"))
    )
    (comp (ref "J6")
      (value "PJ301_THONKICONN6")
      (footprint "eagle-import:WQP_PJ_301M6")
      (libsource (lib "eagle-import") (part "PJ301_THONKICONN6"))
    )
    (comp (ref "J7")
      (value "PJ301_THONKICONN6")
      (footprint "eagle-import:WQP_PJ_301M6")
      (libsource (lib "eagle-import") (part "PJ301_THONKICONN6"))
    )
    (comp (ref "J8")
      (value "PJ301_THONKICONN6")
      (footprint "eagle-import:WQP_PJ_301M6")
      (libsource (lib "eagle-import") (part "PJ301_THONKICONN6"))
    )
    (comp (ref "J18")
      (value "PJ301_THONKICONN6")
      (footprint "eagle-import:WQP_PJ_301M6")
      (libsource (lib "eagle-import") (part "PJ301_THONKICONN6"))
    )
    (comp (ref "J19")
      (value "PJ301_THONKICONN6")
      (footprint "eagle-import:WQP_PJ_301M6")
      (libsource (lib "eagle-import") (part "PJ301_THONKICONN6"))
    )
    (comp (ref "J20")
      (value "PJ301_THONKICONN6")
      (footprint "eagle-import:WQP_PJ_301M6")
      (libsource (lib "eagle-import") (part "PJ301_THONKICONN6"))
    )
    (comp (ref "R65")
      (value "10kB")
      (footprint "eagle-import:ALPS_POT_VERTICAL")
      (libsource (lib "eagle-import") (part "POT_USVERTICAL"))
    )
    (comp (ref "R68")
      (value "10kB")
      (footprint "eagle-import:ALPS_POT_VERTICAL_PS")
      (libsource (lib "eagle-import") (part "POT_USVERTICAL_PS"))
    )
    (comp (ref "R69")
      (value "10kB")
      (footprint "eagle-import:ALPS_POT_VERTICAL_PS")
      (libsource (lib "eagle-import") (part "POT_USVERTICAL_PS"))
    )
    (comp (ref "R70")
      (value "150k")
      (footprint "eagle-import:R0603")
      (libsource (lib "eagle-import") (part "R-US_R0603"))
    )
    (comp (ref "R71")
      (value "100k")
      (footprint "eagle-import:R0603")
      (libsource (lib "eagle-import") (part "R-US_R0603"))
    )
    (comp (ref "R72")
      (value "100k")
      (footprint "eagle-import:R0603")
      (libsource (lib "eagle-import") (part "R-US_R0603"))
    )
    (comp (ref "R73")
      (value "100k")
      (footprint "eagle-import:R0603")
      (libsource (lib "eagle-import") (part "R-US_R0603"))
    )
    (comp (ref "R74")
      (value "100k")
      (footprint "eagle-import:R0603")
      (libsource (lib "eagle-import") (part "R-US_R0603"))
    )
    (comp (ref "R75")
      (value "100k")
      (footprint "eagle-import:R0603")
      (libsource (lib "eagle-import") (part "R-US_R0603"))
    )
    (comp (ref "R76")
      (value "100k")
      (footprint "eagle-import:R0603")
      (libsource (lib "eagle-import") (part "R-US_R0603"))
    )
    (comp (ref "R77")
      (value "100k")
      (footprint "eagle-import:R0603")
      (libsource (lib "eagle-import") (part "R-US_R0603"))
    )
    (comp (ref "R78")
      (value "120k")
      (footprint "eagle-import:R0603")
      (libsource (lib "eagle-import") (part "R-US_R0603"))
    )
    (comp (ref "R79")
      (value "120k")
      (footprint "eagle-import:R0603")
      (libsource (lib "eagle-import") (part "R-US_R0603"))
    )
    (comp (ref "R80")
      (value "200k")
      (footprint "eagle-import:R0603")
      (libsource (lib "eagle-import") (part "R-US_R0603"))
    )
    (comp (ref "R81")
      (value "100k")
      (footprint "eagle-import:R0603")
      (libsource (lib "eagle-import") (part "R-US_R0603"))
    )
    (comp (ref "R82")
      (value "100k")
      (footprint "eagle-import:R0603")
      (libsource (lib "eagle-import") (part "R-US_R0603"))
    )
    (comp (ref "R83")
      (value "100k")
      (footprint "eagle-import:R0603")
      (libsource (lib "eagle-import") (part "R-US_R0603"))
    )
    (comp (ref "R84")
      (value "12k")
      (footprint "eagle-import:R0603")
      (libsource (lib "eagle-import") (part "R-US_R0603"))
    )
    (comp (ref "R85")
      (value "18k")
      (footprint "eagle-import:R0603")
      (libsource (lib "eagle-import") (part "R-US_R0603"))
    )
    (comp (ref "R86")
      (value "100k")
      (footprint "eagle-import:R0603")
      (libsource (lib "eagle-import") (part "R-US_R0603"))
    )
    (comp (ref "R87")
      (value "100k")
      (footprint "eagle-import:R0603")
      (libsource (lib "eagle-import") (part "R-US_R0603"))
    )
    (comp (ref "R88")
      (value "100k")
      (footprint "eagle-import:R0603")
      (libsource (lib "eagle-import") (part "R-US_R0603"))
    )
    (comp (ref "R89")
      (value "510")
      (footprint "eagle-import:R0603")
      (libsource (lib "eagle-import") (part "R-US_R0603"))
    )
    (comp (ref "R90")
      (value "510")
      (footprint "eagle-import:R0603")
      (libsource (lib "eagle-import") (part "R-US_R0603"))
    )
    (comp (ref "R91")
      (value "100k")
      (footprint "eagle-import:R0603")
      (libsource (lib "eagle-import") (part "R-US_R0603"))
    )
    (comp (ref "R92")
      (value "100k")
      (footprint "eagle-import:R0603")
      (libsource (lib "eagle-import") (part "R-US_R0603"))
    )
    (comp (ref "R93")
      (value "22k")
      (footprint "eagle-import:R0603")
      (libsource (lib "eagle-import") (part "R-US_R0603"))
    )
    (comp (ref "R94")
      (value "510")
      (footprint "eagle-import:R0603")
      (libsource (lib "eagle-import") (part "R-US_R0603"))
    )
    (comp (ref "R95")
      (value "150k")
      (footprint "eagle-import:R0603")
      (libsource (lib "eagle-import") (part "R-US_R0603"))
    )
    (comp (ref "R97")
      (value "510")
      (footprint "eagle-import:R0603")
      (libsource (lib "eagle-import") (part "R-US_R0603"))
    )
    (comp (ref "R98")
      (value "100k")
      (footprint "eagle-import:R0603")
      (libsource (lib "eagle-import") (part "R-US_R0603"))
    )
    (comp (ref "R99")
      (value "100k")
      (footprint "eagle-import:R0603")
      (libsource (lib "eagle-import") (part "R-US_R0603"))
    )
    (comp (ref "R126")
      (value "1.0k")
      (footprint "eagle-import:R0603")
      (libsource (lib "eagle-import") (part "R-US_R0603"))
    )
    (comp (ref "R127")
      (value "1.0k")
      (footprint "eagle-import:R0603")
      (libsource (lib "eagle-import") (part "R-US_R0603"))
    )
    (comp (ref "R128")
      (value "1.0k")
      (footprint "eagle-import:R0603")
      (libsource (lib "eagle-import") (part "R-US_R0603"))
    )
  )
  (nets
    (net (code "1") (name "AREF_+10") (class "Default")
      (node (ref "C3") (pin "1") (pinfunction "1_1") (pintype "passive"))
      (node (ref "IC1") (pin "1") (pinfunction "C_1") (pintype "passive"))
      (node (ref "R1") (pin "2") (pinfunction "2_2") (pintype "passive"))
      (node (ref "R118") (pin "2") (pinfunction "2_2") (pintype "passive"))
      (node (ref "R121") (pin "2") (pinfunction "2_2") (pintype "passive"))
      (node (ref "R28") (pin "1") (pinfunction "1_1") (pintype "passive"))
      (node (ref "R29") (pin "1") (pinfunction "1_1") (pintype "passive"))
      (node (ref "R46") (pin "1") (pinfunction "1_1") (pintype "passive"))
      (node (ref "R80") (pin "1") (pinfunction "1_1") (pintype "passive"))
    )
    (net (code "2") (name "AREF_-10") (class "Default")
      (node (ref "C4") (pin "1") (pinfunction "1_1") (pintype "passive"))
      (node (ref "IC2") (pin "2") (pinfunction "A_2") (pintype "passive"))
      (node (ref "R108") (pin "1") (pinfunction "1_1") (pintype "passive"))
      (node (ref "R109") (pin "1") (pinfunction "1_1") (pintype "passive"))
      (node (ref "R12") (pin "1") (pinfunction "1_1") (pintype "passive"))
      (node (ref "R2") (pin "2") (pinfunction "2_2") (pintype "passive"))
      (node (ref "R43") (pin "1") (pinfunction "1_1") (pintype "passive"))
      (node (ref "R49") (pin "1") (pinfunction "1_1") (pintype "passive"))
      (node (ref "R5") (pin "1") (pinfunction "1_1") (pintype "passive"))
      (node (ref "R54") (pin "1") (pinfunction "1_1") (pintype "passive"))
      (node (ref "R70") (pin "1") (pinfunction "1_1") (pintype "passive"))
      (node (ref "R77") (pin "1") (pinfunction "1_1") (pintype "passive"))
      (node (ref "R83") (pin "1") (pinfunction "1_1") (pintype "passive"))
    )
    (net (code "3") (name "BP_1") (class "Default")
      (node (ref "C40") (pin "2") (pinfunction "2_2") (pintype "passive"))
      (node (ref "IC9") (pin "7") (pinfunction "OUT_7") (pintype "output"))
      (node (ref "R127") (pin "1") (pinfunction "1_1") (pintype "passive"))
      (node (ref "R87") (pin "1") (pinfunction "1_1") (pintype "passive"))
      (node (ref "R98") (pin "1") (pinfunction "1_1") (pintype "passive"))
    )
    (net (code "4") (name "BP_2") (class "Default")
      (node (ref "C25") (pin "2") (pinfunction "2_2") (pintype "passive"))
      (node (ref "IC6") (pin "7") (pinfunction "OUT_7") (pintype "output"))
      (node (ref "R124") (pin "1") (pinfunction "1_1") (pintype "passive"))
      (node (ref "R53") (pin "1") (pinfunction "1_1") (pintype "passive"))
      (node (ref "R66") (pin "1") (pinfunction "1_1") (pintype "passive"))
    )
    (net (code "5") (name "F_GLOBAL") (class "Default")
      (node (ref "J11") (pin "P3") (pinfunction "3_P3") (pintype "passive"))
      (node (ref "R47") (pin "1") (pinfunction "1_1") (pintype "passive"))
      (node (ref "R7") (pin "1") (pinfunction "1_1") (pintype "passive"))
      (node (ref "R8") (pin "1") (pinfunction "1_1") (pintype "passive"))
      (node (ref "R81") (pin "1") (pinfunction "1_1") (pintype "passive"))
    )
    (net (code "6") (name "GAIN_GLOBAL") (class "Default")
      (node (ref "J12") (pin "P3") (pinfunction "3_P3") (pintype "passive"))
      (node (ref "R26") (pin "1") (pinfunction "1_1") (pintype "passive"))
      (node (ref "R31") (pin "1") (pinfunction "1_1") (pintype "passive"))
      (node (ref "R44") (pin "1") (pinfunction "1_1") (pintype "passive"))
      (node (ref "R79") (pin "1") (pinfunction "1_1") (pintype "passive"))
    )
    (net (code "7") (name "GND") (class "Default")
      (node (ref "C1") (pin "-") (pinfunction "-_-") (pintype "passive"))
      (node (ref "C12") (pin "2") (pinfunction "2_2") (pintype "passive"))
      (node (ref "C13") (pin "1") (pinfunction "1_1") (pintype "passive"))
      (node (ref "C14") (pin "2") (pinfunction "2_2") (pintype "passive"))
      (node (ref "C15") (pin "2") (pinfunction "2_2") (pintype "passive"))
      (node (ref "C18") (pin "2") (pinfunction "2_2") (pintype "passive"))
      (node (ref "C19") (pin "2") (pinfunction "2_2") (pintype "passive"))
      (node (ref "C2") (pin "+") (pinfunction "+_+") (pintype "passive"))
      (node (ref "C20") (pin "1") (pinfunction "1_1") (pintype "passive"))
      (node (ref "C21") (pin "2") (pinfunction "2_2") (pintype "passive"))
      (node (ref "C22") (pin "1") (pinfunction "1_1") (pintype "passive"))
      (node (ref "C27") (pin "2") (pinfunction "2_2") (pintype "passive"))
      (node (ref "C28") (pin "1") (pinfunction "1_1") (pintype "passive"))
      (node (ref "C29") (pin "2") (pinfunction "2_2") (pintype "passive"))
      (node (ref "C3") (pin "2") (pinfunction "2_2") (pintype "passive"))
      (node (ref "C30") (pin "2") (pinfunction "2_2") (pintype "passive"))
      (node (ref "C31") (pin "2") (pinfunction "2_2") (pintype "passive"))
      (node (ref "C33") (pin "2") (pinfunction "2_2") (pintype "passive"))
      (node (ref "C34") (pin "2") (pinfunction "2_2") (pintype "passive"))
      (node (ref "C35") (pin "1") (pinfunction "1_1") (pintype "passive"))
      (node (ref "C36") (pin "2") (pinfunction "2_2") (pintype "passive"))
      (node (ref "C37") (pin "1") (pinfunction "1_1") (pintype "passive"))
      (node (ref "C4") (pin "2") (pinfunction "2_2") (pintype "passive"))
      (node (ref "C42") (pin "2") (pinfunction "2_2") (pintype "passive"))
      (node (ref "C43") (pin "2") (pinfunction "2_2") (pintype "passive"))
      (node (ref "C44") (pin "1") (pinfunction "1_1") (pintype "passive"))
      (node (ref "C45") (pin "2") (pinfunction "2_2") (pintype "passive"))
      (node (ref "C47") (pin "2") (pinfunction "2_2") (pintype "passive"))
      (node (ref "C48") (pin "2") (pinfunction "2_2") (pintype "passive"))
      (node (ref "C49") (pin "2") (pinfunction "2_2") (pintype "passive"))
      (node (ref "C5") (pin "2") (pinfunction "2_2") (pintype "passive"))
      (node (ref "C50") (pin "2") (pinfunction "2_2") (pintype "passive"))
      (node (ref "C51") (pin "1") (pinfunction "1_1") (pintype "passive"))
      (node (ref "C52") (pin "2") (pinfunction "2_2") (pintype "passive"))
      (node (ref "C53") (pin "1") (pinfunction "1_1") (pintype "passive"))
      (node (ref "C54") (pin "1") (pinfunction "1_1") (pintype "passive"))
      (node (ref "C55") (pin "2") (pinfunction "2_2") (pintype "passive"))
      (node (ref "C56") (pin "2") (pinfunction "2_2") (pintype "passive"))
      (node (ref "C58") (pin "-") (pinfunction "-_-") (pintype "passive"))
      (node (ref "C8") (pin "1") (pinfunction "1_1") (pintype "passive"))
      (node (ref "C9") (pin "2") (pinfunction "2_2") (pintype "passive"))
      (node (ref "D1") (pin "C") (pinfunction "C_C") (pintype "passive"))
      (node (ref "D10") (pin "A") (pinfunction "A_A") (pintype "passive"))
      (node (ref "D3") (pin "A") (pinfunction "A_A") (pintype "passive"))
      (node (ref "D4") (pin "A") (pinfunction "A_A") (pintype "passive"))
      (node (ref "D5") (pin "A") (pinfunction "A_A") (pintype "passive"))
      (node (ref "D6") (pin "A") (pinfunction "A_A") (pintype "passive"))
      (node (ref "D7") (pin "A") (pinfunction "A_A") (pintype "passive"))
      (node (ref "IC1") (pin "2") (pinfunction "A_2") (pintype "passive"))
      (node (ref "IC10") (pin "10") (pinfunction "+IN_10") (pintype "input"))
      (node (ref "IC10") (pin "12") (pinfunction "+IN_12") (pintype "input"))
      (node (ref "IC10") (pin "3") (pinfunction "+IN_3") (pintype "input"))
      (node (ref "IC10") (pin "5") (pinfunction "+IN_5") (pintype "input"))
      (node (ref "IC11") (pin "8") (pinfunction "GND_8") (pintype "power_in"))
      (node (ref "IC12") (pin "3") (pinfunction "+IN_3") (pintype "input"))
      (node (ref "IC12") (pin "5") (pinfunction "+IN_5") (pintype "input"))
      (node (ref "IC13") (pin "3") (pinfunction "+IN_3") (pintype "input"))
      (node (ref "IC13") (pin "5") (pinfunction "+IN_5") (pintype "input"))
      (node (ref "IC14") (pin "4") (pinfunction "V-_4") (pintype "power_in"))
      (node (ref "IC2") (pin "1") (pinfunction "C_1") (pintype "passive"))
      (node (ref "IC3") (pin "3") (pinfunction "+IN_3") (pintype "input"))
      (node (ref "IC3") (pin "5") (pinfunction "+IN_5") (pintype "input"))
      (node (ref "IC4") (pin "10") (pinfunction "+IN_10") (pintype "input"))
      (node (ref "IC4") (pin "12") (pinfunction "+IN_12") (pintype "input"))
      (node (ref "IC4") (pin "3") (pinfunction "+IN_3") (pintype "input"))
      (node (ref "IC4") (pin "5") (pinfunction "+IN_5") (pintype "input"))
      (node (ref "IC5") (pin "8") (pinfunction "GND_8") (pintype "power_in"))
      (node (ref "IC6") (pin "10") (pinfunction "+IN_10") (pintype "input"))
      (node (ref "IC6") (pin "12") (pinfunction "+IN_12") (pintype "input"))
      (node (ref "IC6") (pin "3") (pinfunction "+IN_3") (pintype "input"))
      (node (ref "IC6") (pin "5") (pinfunction "+IN_5") (pintype "input"))
      (node (ref "IC7") (pin "10") (pinfunction "+IN_10") (pintype "input"))
      (node (ref "IC7") (pin "12") (pinfunction "+IN_12") (pintype "input"))
      (node (ref "IC7") (pin "3") (pinfunction "+IN_3") (pintype "input"))
      (node (ref "IC7") (pin "5") (pinfunction "+IN_5") (pintype "input"))
      (node (ref "IC8") (pin "8") (pinfunction "GND_8") (pintype "power_in"))
      (node (ref "IC9") (pin "10") (pinfunction "+IN_10") (pintype "input"))
      (node (ref "IC9") (pin "12") (pinfunction "+IN_12") (pintype "input"))
      (node (ref "IC9") (pin "3") (pinfunction "+IN_3") (pintype "input"))
      (node (ref "IC9") (pin "5") (pinfunction "+IN_5") (pintype "input"))
      (node (ref "J1") (pin "P1") (pinfunction "1_P1") (pintype "passive"))
      (node (ref "J10") (pin "P1") (pinfunction "1_P1") (pintype "passive"))
      (node (ref "J11") (pin "P1") (pinfunction "1_P1") (pintype "passive"))
      (node (ref "J12") (pin "P1") (pinfunction "1_P1") (pintype "passive"))
      (node (ref "J13") (pin "P1") (pinfunction "1_P1") (pintype "passive"))
      (node (ref "J14") (pin "P1") (pinfunction "1_P1") (pintype "passive"))
      (node (ref "J15") (pin "P1") (pinfunction "1_P1") (pintype "passive"))
      (node (ref "J16") (pin "P1") (pinfunction "1_P1") (pintype "passive"))
      (node (ref "J17") (pin "P1") (pinfunction "1_P1") (pintype "passive"))
      (node (ref "J18") (pin "P1") (pinfunction "1_P1") (pintype "passive"))
      (node (ref "J19") (pin "P1") (pinfunction "1_P1") (pintype "passive"))
      (node (ref "J2") (pin "P1") (pinfunction "1_P1") (pintype "passive"))
      (node (ref "J20") (pin "P1") (pinfunction "1_P1") (pintype "passive"))
      (node (ref "J3") (pin "P1") (pinfunction "1_P1") (pintype "passive"))
      (node (ref "J4") (pin "P1") (pinfunction "1_P1") (pintype "passive"))
      (node (ref "J5") (pin "P1") (pinfunction "1_P1") (pintype "passive"))
      (node (ref "J6") (pin "P1") (pinfunction "1_P1") (pintype "passive"))
      (node (ref "J7") (pin "P1") (pinfunction "1_P1") (pintype "passive"))
      (node (ref "J8") (pin "P1") (pinfunction "1_P1") (pintype "passive"))
      (node (ref "J9") (pin "P1") (pinfunction "1_P1") (pintype "passive"))
      (node (ref "JP11") (pin "3") (pinfunction "3_3") (pintype "passive"))
      (node (ref "JP11") (pin "4") (pinfunction "4_4") (pintype "passive"))
      (node (ref "JP11") (pin "5") (pinfunction "5_5") (pintype "passive"))
      (node (ref "JP11") (pin "6") (pinfunction "6_6") (pintype "passive"))
      (node (ref "JP11") (pin "7") (pinfunction "7_7") (pintype "passive"))
      (node (ref "JP11") (pin "8") (pinfunction "8_8") (pintype "passive"))
      (node (ref "Q1") (pin "E") (pinfunction "E_E") (pintype "passive"))
      (node (ref "R100") (pin "P$1") (pinfunction "E_P$1") (pintype "passive"))
      (node (ref "R101") (pin "P$1") (pinfunction "E_P$1") (pintype "passive"))
      (node (ref "R116") (pin "1") (pinfunction "1_1") (pintype "passive"))
      (node (ref "R117") (pin "1") (pinfunction "1_1") (pintype "passive"))
      (node (ref "R120") (pin "1") (pinfunction "1_1") (pintype "passive"))
      (node (ref "R3") (pin "P$1") (pinfunction "E_P$1") (pintype "passive"))
      (node (ref "R34") (pin "P$1") (pinfunction "E_P$1") (pintype "passive"))
      (node (ref "R36") (pin "P$1") (pinfunction "E_P$1") (pintype "passive"))
      (node (ref "R4") (pin "P$1") (pinfunction "E_P$1") (pintype "passive"))
      (node (ref "R42") (pin "P$3") (pinfunction "A_P$3") (pintype "passive"))
      (node (ref "R65") (pin "P$3") (pinfunction "A_P$3") (pintype "passive"))
      (node (ref "R68") (pin "P$1") (pinfunction "E_P$1") (pintype "passive"))
      (node (ref "R69") (pin "P$1") (pinfunction "E_P$1") (pintype "passive"))
    )
    (net (code "8") (name "HP_1") (class "Default")
      (node (ref "IC9") (pin "1") (pinfunction "OUT_1") (pintype "output"))
      (node (ref "R126") (pin "1") (pinfunction "1_1") (pintype "passive"))
      (node (ref "R75") (pin "2") (pinfunction "2_2") (pintype "passive"))
      (node (ref "R86") (pin "1") (pinfunction "1_1") (pintype "passive"))
    )
    (net (code "9") (name "HP_2") (class "Default")
      (node (ref "IC6") (pin "1") (pinfunction "OUT_1") (pintype "output"))
      (node (ref "R123") (pin "1") (pinfunction "1_1") (pintype "passive"))
      (node (ref "R40") (pin "2") (pinfunction "2_2") (pintype "passive"))
      (node (ref "R52") (pin "1") (pinfunction "1_1") (pintype "passive"))
    )
    (net (code "10") (name "IN") (class "Default")
      (node (ref "IC12") (pin "7") (pinfunction "OUT_7") (pintype "output"))
      (node (ref "JP5") (pin "3") (pinfunction "3_3") (pintype "passive"))
      (node (ref "R103") (pin "2") (pinfunction "2_2") (pintype "passive"))
      (node (ref "R15") (pin "1") (pinfunction "1_1") (pintype "passive"))
      (node (ref "R16") (pin "1") (pinfunction "1_1") (pintype "passive"))
      (node (ref "R17") (pin "1") (pinfunction "1_1") (pintype "passive"))
      (node (ref "R37") (pin "1") (pinfunction "1_1") (pintype "passive"))
      (node (ref "R72") (pin "1") (pinfunction "1_1") (pintype "passive"))
    )
    (net (code "11") (name "MINUS_BUS") (class "Default")
      (node (ref "IC11") (pin "12") (pinfunction "OUT_12") (pintype "output"))
      (node (ref "IC13") (pin "2") (pinfunction "-IN_2") (pintype "input"))
      (node (ref "IC5") (pin "5") (pinfunction "OUT_5") (pintype "output"))
      (node (ref "IC8") (pin "12") (pinfunction "OUT_12") (pintype "output"))
      (node (ref "R104") (pin "2") (pinfunction "2_2") (pintype "passive"))
      (node (ref "R107") (pin "1") (pinfunction "1_1") (pintype "passive"))
      (node (ref "R19") (pin "2") (pinfunction "2_2") (pintype "passive"))
    )
    (net (code "12") (name "Net-(C14-Pad1)") (class "Default")
      (node (ref "C14") (pin "1") (pinfunction "1_1") (pintype "passive"))
      (node (ref "R21") (pin "1") (pinfunction "1_1") (pintype "passive"))
    )
    (net (code "13") (name "Net-(C15-Pad1)") (class "Default")
      (node (ref "C15") (pin "1") (pinfunction "1_1") (pintype "passive"))
      (node (ref "R20") (pin "1") (pinfunction "1_1") (pintype "passive"))
    )
    (net (code "14") (name "Net-(C18-Pad1)") (class "Default")
      (node (ref "C18") (pin "1") (pinfunction "1_1") (pintype "passive"))
      (node (ref "R24") (pin "1") (pinfunction "1_1") (pintype "passive"))
    )
    (net (code "15") (name "Net-(C19-Pad1)") (class "Default")
      (node (ref "C19") (pin "1") (pinfunction "1_1") (pintype "passive"))
      (node (ref "R25") (pin "1") (pinfunction "1_1") (pintype "passive"))
    )
    (net (code "16") (name "Net-(C29-Pad1)") (class "Default")
      (node (ref "C29") (pin "1") (pinfunction "1_1") (pintype "passive"))
      (node (ref "R56") (pin "1") (pinfunction "1_1") (pintype "passive"))
    )
    (net (code "17") (name "Net-(C30-Pad1)") (class "Default")
      (node (ref "C30") (pin "1") (pinfunction "1_1") (pintype "passive"))
      (node (ref "R57") (pin "1") (pinfunction "1_1") (pintype "passive"))
    )
    (net (code "18") (name "Net-(C33-Pad1)") (class "Default")
      (node (ref "C33") (pin "1") (pinfunction "1_1") (pintype "passive"))
      (node (ref "R61") (pin "1") (pinfunction "1_1") (pintype "passive"))
    )
    (net (code "19") (name "Net-(C34-Pad1)") (class "Default")
      (node (ref "C34") (pin "1") (pinfunction "1_1") (pintype "passive"))
      (node (ref "R64") (pin "1") (pinfunction "1_1") (pintype "passive"))
    )
    (net (code "20") (name "Net-(C45-Pad1)") (class "Default")
      (node (ref "C45") (pin "1") (pinfunction "1_1") (pintype "passive"))
      (node (ref "R89") (pin "1") (pinfunction "1_1") (pintype "passive"))
    )
    (net (code "21") (name "Net-(C47-Pad1)") (class "Default")
      (node (ref "C47") (pin "1") (pinfunction "1_1") (pintype "passive"))
      (node (ref "R90") (pin "1") (pinfunction "1_1") (pintype "passive"))
    )
    (net (code "22") (name "Net-(C48-Pad1)") (class "Default")
      (node (ref "C48") (pin "1") (pinfunction "1_1") (pintype "passive"))
      (node (ref "R94") (pin "1") (pinfunction "1_1") (pintype "passive"))
    )
    (net (code "23") (name "Net-(C49-Pad1)") (class "Default")
      (node (ref "C49") (pin "1") (pinfunction "1_1") (pintype "passive"))
      (node (ref "R97") (pin "1") (pinfunction "1_1") (pintype "passive"))
    )
    (net (code "24") (name "Net-(C55-Pad1)") (class "Default")
      (node (ref "C55") (pin "1") (pinfunction "1_1") (pintype "passive"))
      (node (ref "R113") (pin "2") (pinfunction "2_2") (pintype "passive"))
      (node (ref "R114") (pin "1") (pinfunction "1_1") (pintype "passive"))
    )
    (net (code "25") (name "Net-(C57-Pad1)") (class "Default")
      (node (ref "C57") (pin "1") (pinfunction "1_1") (pintype "passive"))
      (node (ref "R115") (pin "1") (pinfunction "1_1") (pintype "passive"))
    )
    (net (code "26") (name "Net-(D2-PadA)") (class "Default")
      (node (ref "D2") (pin "A") (pinfunction "A_A") (pintype "passive"))
      (node (ref "JP11") (pin "1") (pinfunction "1_1") (pintype "passive"))
      (node (ref "JP11") (pin "2") (pinfunction "2_2") (pintype "passive"))
    )
    (net (code "27") (name "Net-(D13-PadC)") (class "Default")
      (node (ref "D13") (pin "C") (pinfunction "C_C") (pintype "passive"))
      (node (ref "D14") (pin "C") (pinfunction "C_C") (pintype "passive"))
      (node (ref "R113") (pin "1") (pinfunction "1_1") (pintype "passive"))
    )
    (net (code "28") (name "Net-(IC3A--IN)") (class "Default")
      (node (ref "C6") (pin "1") (pinfunction "1_1") (pintype "passive"))
      (node (ref "IC3") (pin "2") (pinfunction "-IN_2") (pintype "input"))
      (node (ref "IC5") (pin "4") (pinfunction "OUT_4") (pintype "output"))
    )
    (net (code "29") (name "Net-(IC3A-OUT)") (class "Default")
      (node (ref "C6") (pin "2") (pinfunction "2_2") (pintype "passive"))
      (node (ref "IC3") (pin "1") (pinfunction "OUT_1") (pintype "output"))
      (node (ref "R11") (pin "2") (pinfunction "2_2") (pintype "passive"))
      (node (ref "R32") (pin "1") (pinfunction "1_1") (pintype "passive"))
      (node (ref "R33") (pin "1") (pinfunction "1_1") (pintype "passive"))
    )
    (net (code "30") (name "Net-(IC3B--IN)") (class "Default")
      (node (ref "C7") (pin "1") (pinfunction "1_1") (pintype "passive"))
      (node (ref "IC3") (pin "6") (pinfunction "-IN_6") (pintype "input"))
      (node (ref "IC5") (pin "13") (pinfunction "OUT_13") (pintype "output"))
    )
    (net (code "31") (name "Net-(IC3B-OUT)") (class "Default")
      (node (ref "C7") (pin "2") (pinfunction "2_2") (pintype "passive"))
      (node (ref "IC3") (pin "7") (pinfunction "OUT_7") (pintype "output"))
      (node (ref "R10") (pin "2") (pinfunction "2_2") (pintype "passive"))
      (node (ref "R18") (pin "1") (pinfunction "1_1") (pintype "passive"))
      (node (ref "R19") (pin "1") (pinfunction "1_1") (pintype "passive"))
    )
    (net (code "32") (name "Net-(IC4A--IN)") (class "Default")
      (node (ref "C10") (pin "2") (pinfunction "2_2") (pintype "passive"))
      (node (ref "IC4") (pin "2") (pinfunction "-IN_2") (pintype "input"))
      (node (ref "R13") (pin "1") (pinfunction "1_1") (pintype "passive"))
      (node (ref "R3") (pin "P$3") (pinfunction "A_P$3") (pintype "passive"))
      (node (ref "R6") (pin "2") (pinfunction "2_2") (pintype "passive"))
      (node (ref "R7") (pin "2") (pinfunction "2_2") (pintype "passive"))
    )
    (net (code "33") (name "Net-(IC4A-OUT)") (class "Default")
      (node (ref "C10") (pin "1") (pinfunction "1_1") (pintype "passive"))
      (node (ref "D3") (pin "C") (pinfunction "C_C") (pintype "passive"))
      (node (ref "IC4") (pin "1") (pinfunction "OUT_1") (pintype "output"))
      (node (ref "IC5") (pin "14") (pinfunction "CTRL_14") (pintype "input"))
      (node (ref "R13") (pin "2") (pinfunction "2_2") (pintype "passive"))
    )
    (net (code "34") (name "Net-(IC4B--IN)") (class "Default")
      (node (ref "C16") (pin "2") (pinfunction "2_2") (pintype "passive"))
      (node (ref "IC4") (pin "6") (pinfunction "-IN_6") (pintype "input"))
      (node (ref "R101") (pin "P$3") (pinfunction "A_P$3") (pintype "passive"))
      (node (ref "R22") (pin "1") (pinfunction "1_1") (pintype "passive"))
      (node (ref "R26") (pin "2") (pinfunction "2_2") (pintype "passive"))
      (node (ref "R27") (pin "2") (pinfunction "2_2") (pintype "passive"))
      (node (ref "R28") (pin "2") (pinfunction "2_2") (pintype "passive"))
    )
    (net (code "35") (name "Net-(IC4B-OUT)") (class "Default")
      (node (ref "C16") (pin "1") (pinfunction "1_1") (pintype "passive"))
      (node (ref "D6") (pin "C") (pinfunction "C_C") (pintype "passive"))
      (node (ref "IC4") (pin "7") (pinfunction "OUT_7") (pintype "output"))
      (node (ref "IC5") (pin "6") (pinfunction "CTRL_6") (pintype "input"))
      (node (ref "R22") (pin "2") (pinfunction "2_2") (pintype "passive"))
    )
    (net (code "36") (name "Net-(IC4C--IN)") (class "Default")
      (node (ref "C17") (pin "2") (pinfunction "2_2") (pintype "passive"))
      (node (ref "IC4") (pin "9") (pinfunction "-IN_9") (pintype "input"))
      (node (ref "R23") (pin "1") (pinfunction "1_1") (pintype "passive"))
      (node (ref "R29") (pin "2") (pinfunction "2_2") (pintype "passive"))
      (node (ref "R30") (pin "2") (pinfunction "2_2") (pintype "passive"))
      (node (ref "R31") (pin "2") (pinfunction "2_2") (pintype "passive"))
      (node (ref "R4") (pin "P$3") (pinfunction "A_P$3") (pintype "passive"))
    )
    (net (code "37") (name "Net-(IC4C-OUT)") (class "Default")
      (node (ref "C17") (pin "1") (pinfunction "1_1") (pintype "passive"))
      (node (ref "D5") (pin "C") (pinfunction "C_C") (pintype "passive"))
      (node (ref "IC4") (pin "8") (pinfunction "OUT_8") (pintype "output"))
      (node (ref "IC5") (pin "11") (pinfunction "CTRL_11") (pintype "input"))
      (node (ref "R23") (pin "2") (pinfunction "2_2") (pintype "passive"))
    )
    (net (code "38") (name "Net-(IC4D--IN)") (class "Default")
      (node (ref "C11") (pin "2") (pinfunction "2_2") (pintype "passive"))
      (node (ref "IC4") (pin "13") (pinfunction "-IN_13") (pintype "input"))
      (node (ref "R100") (pin "P$3") (pinfunction "A_P$3") (pintype "passive"))
      (node (ref "R14") (pin "1") (pinfunction "1_1") (pintype "passive"))
      (node (ref "R8") (pin "2") (pinfunction "2_2") (pintype "passive"))
      (node (ref "R9") (pin "2") (pinfunction "2_2") (pintype "passive"))
    )
    (net (code "39") (name "Net-(IC4D-OUT)") (class "Default")
      (node (ref "C11") (pin "1") (pinfunction "1_1") (pintype "passive"))
      (node (ref "D4") (pin "C") (pinfunction "C_C") (pintype "passive"))
      (node (ref "IC4") (pin "14") (pinfunction "OUT_14") (pintype "output"))
      (node (ref "IC5") (pin "3") (pinfunction "CTRL_3") (pintype "input"))
      (node (ref "R14") (pin "2") (pinfunction "2_2") (pintype "passive"))
    )
    (net (code "40") (name "Net-(IC5A-IN)") (class "Default")
      (node (ref "IC5") (pin "2") (pinfunction "IN_2") (pintype "input"))
      (node (ref "R11") (pin "1") (pinfunction "1_1") (pintype "passive"))
      (node (ref "R15") (pin "2") (pinfunction "2_2") (pintype "passive"))
      (node (ref "R20") (pin "2") (pinfunction "2_2") (pintype "passive"))
    )
    (net (code "41") (name "Net-(IC5B-IN)") (class "Default")
      (node (ref "IC5") (pin "7") (pinfunction "IN_7") (pintype "input"))
      (node (ref "R25") (pin "2") (pinfunction "2_2") (pintype "passive"))
      (node (ref "R32") (pin "2") (pinfunction "2_2") (pintype "passive"))
    )
    (net (code "42") (name "Net-(IC5C-IN)") (class "Default")
      (node (ref "IC5") (pin "10") (pinfunction "IN_10") (pintype "input"))
      (node (ref "R17") (pin "2") (pinfunction "2_2") (pintype "passive"))
      (node (ref "R18") (pin "2") (pinfunction "2_2") (pintype "passive"))
      (node (ref "R24") (pin "2") (pinfunction "2_2") (pintype "passive"))
    )
    (net (code "43") (name "Net-(IC5D-IN)") (class "Default")
      (node (ref "IC5") (pin "15") (pinfunction "IN_15") (pintype "input"))
      (node (ref "R10") (pin "1") (pinfunction "1_1") (pintype "passive"))
      (node (ref "R16") (pin "2") (pinfunction "2_2") (pintype "passive"))
      (node (ref "R21") (pin "2") (pinfunction "2_2") (pintype "passive"))
    )
    (net (code "44") (name "Net-(IC6A--IN)") (class "Default")
      (node (ref "IC6") (pin "2") (pinfunction "-IN_2") (pintype "input"))
      (node (ref "R35") (pin "1") (pinfunction "1_1") (pintype "passive"))
      (node (ref "R37") (pin "2") (pinfunction "2_2") (pintype "passive"))
      (node (ref "R38") (pin "1") (pinfunction "1_1") (pintype "passive"))
      (node (ref "R40") (pin "1") (pinfunction "1_1") (pintype "passive"))
    )
    (net (code "45") (name "Net-(IC6B--IN)") (class "Default")
      (node (ref "C25") (pin "1") (pinfunction "1_1") (pintype "passive"))
      (node (ref "IC6") (pin "6") (pinfunction "-IN_6") (pintype "input"))
      (node (ref "IC8") (pin "4") (pinfunction "OUT_4") (pintype "output"))
    )
    (net (code "46") (name "Net-(IC6C--IN)") (class "Default")
      (node (ref "C26") (pin "1") (pinfunction "1_1") (pintype "passive"))
      (node (ref "IC6") (pin "9") (pinfunction "-IN_9") (pintype "input"))
      (node (ref "IC8") (pin "13") (pinfunction "OUT_13") (pintype "output"))
    )
    (net (code "47") (name "Net-(IC6C-OUT)") (class "Default")
      (node (ref "C26") (pin "2") (pinfunction "2_2") (pintype "passive"))
      (node (ref "IC6") (pin "8") (pinfunction "OUT_8") (pintype "output"))
      (node (ref "R125") (pin "1") (pinfunction "1_1") (pintype "passive"))
      (node (ref "R35") (pin "2") (pinfunction "2_2") (pintype "passive"))
    )
    (net (code "48") (name "Net-(IC6D--IN)") (class "Default")
      (node (ref "IC6") (pin "13") (pinfunction "-IN_13") (pintype "input"))
      (node (ref "IC8") (pin "5") (pinfunction "OUT_5") (pintype "output"))
      (node (ref "R41") (pin "2") (pinfunction "2_2") (pintype "passive"))
    )
    (net (code "49") (name "Net-(IC6D-OUT)") (class "Default")
      (node (ref "IC6") (pin "14") (pinfunction "OUT_14") (pintype "output"))
      (node (ref "R38") (pin "2") (pinfunction "2_2") (pintype "passive"))
      (node (ref "R39") (pin "1") (pinfunction "1_1") (pintype "passive"))
      (node (ref "R55") (pin "1") (pinfunction "1_1") (pintype "passive"))
      (node (ref "R67") (pin "1") (pinfunction "1_1") (pintype "passive"))
    )
    (net (code "50") (name "Net-(IC7A--IN)") (class "Default")
      (node (ref "C23") (pin "2") (pinfunction "2_2") (pintype "passive"))
      (node (ref "IC7") (pin "2") (pinfunction "-IN_2") (pintype "input"))
      (node (ref "R36") (pin "P$3") (pinfunction "A_P$3") (pintype "passive"))
      (node (ref "R44") (pin "2") (pinfunction "2_2") (pintype "passive"))
      (node (ref "R45") (pin "2") (pinfunction "2_2") (pintype "passive"))
      (node (ref "R46") (pin "2") (pinfunction "2_2") (pintype "passive"))
      (node (ref "R50") (pin "1") (pinfunction "1_1") (pintype "passive"))
    )
    (net (code "51") (name "Net-(IC7A-OUT)") (class "Default")
      (node (ref "C23") (pin "1") (pinfunction "1_1") (pintype "passive"))
      (node (ref "D7") (pin "C") (pinfunction "C_C") (pintype "passive"))
      (node (ref "IC7") (pin "1") (pinfunction "OUT_1") (pintype "output"))
      (node (ref "IC8") (pin "11") (pinfunction "CTRL_11") (pintype "input"))
      (node (ref "R50") (pin "2") (pinfunction "2_2") (pintype "passive"))
    )
    (net (code "52") (name "Net-(IC7B--IN)") (class "Default")
      (node (ref "IC7") (pin "6") (pinfunction "-IN_6") (pintype "input"))
      (node (ref "R58") (pin "2") (pinfunction "2_2") (pintype "passive"))
      (node (ref "R59") (pin "1") (pinfunction "1_1") (pintype "passive"))
    )
    (net (code "53") (name "Net-(IC7B-OUT)") (class "Default")
      (node (ref "IC7") (pin "7") (pinfunction "OUT_7") (pintype "output"))
      (node (ref "R59") (pin "2") (pinfunction "2_2") (pintype "passive"))
      (node (ref "R62") (pin "1") (pinfunction "1_1") (pintype "passive"))
    )
    (net (code "54") (name "Net-(IC7C--IN)") (class "Default")
      (node (ref "C32") (pin "2") (pinfunction "2_2") (pintype "passive"))
      (node (ref "D9") (pin "A") (pinfunction "A_A") (pintype "passive"))
      (node (ref "IC7") (pin "9") (pinfunction "-IN_9") (pintype "input"))
      (node (ref "R42") (pin "P$1") (pinfunction "E_P$1") (pintype "passive"))
      (node (ref "R60") (pin "1") (pinfunction "1_1") (pintype "passive"))
      (node (ref "R62") (pin "2") (pinfunction "2_2") (pintype "passive"))
    )
    (net (code "55") (name "Net-(IC7C-OUT)") (class "Default")
      (node (ref "D18") (pin "A") (pinfunction "A_A") (pintype "passive"))
      (node (ref "D9") (pin "C") (pinfunction "C_C") (pintype "passive"))
      (node (ref "IC7") (pin "8") (pinfunction "OUT_8") (pintype "output"))
    )
    (net (code "56") (name "Net-(IC7D--IN)") (class "Default")
      (node (ref "C24") (pin "2") (pinfunction "2_2") (pintype "passive"))
      (node (ref "D8") (pin "A") (pinfunction "A_A") (pintype "passive"))
      (node (ref "IC7") (pin "13") (pinfunction "-IN_13") (pintype "input"))
      (node (ref "R34") (pin "P$3") (pinfunction "A_P$3") (pintype "passive"))
      (node (ref "R47") (pin "2") (pinfunction "2_2") (pintype "passive"))
      (node (ref "R48") (pin "2") (pinfunction "2_2") (pintype "passive"))
      (node (ref "R51") (pin "1") (pinfunction "1_1") (pintype "passive"))
    )
    (net (code "57") (name "Net-(IC7D-OUT)") (class "Default")
      (node (ref "D15") (pin "A") (pinfunction "A_A") (pintype "passive"))
      (node (ref "D8") (pin "C") (pinfunction "C_C") (pintype "passive"))
      (node (ref "IC7") (pin "14") (pinfunction "OUT_14") (pintype "output"))
    )
    (net (code "58") (name "Net-(IC8A-CTRL)") (class "Default")
      (node (ref "C24") (pin "1") (pinfunction "1_1") (pintype "passive"))
      (node (ref "D15") (pin "C") (pinfunction "C_C") (pintype "passive"))
      (node (ref "IC8") (pin "14") (pinfunction "CTRL_14") (pintype "input"))
      (node (ref "IC8") (pin "3") (pinfunction "CTRL_3") (pintype "input"))
      (node (ref "R51") (pin "2") (pinfunction "2_2") (pintype "passive"))
    )
    (net (code "59") (name "Net-(IC8A-IN)") (class "Default")
      (node (ref "IC8") (pin "2") (pinfunction "IN_2") (pintype "input"))
      (node (ref "R52") (pin "2") (pinfunction "2_2") (pintype "passive"))
      (node (ref "R56") (pin "2") (pinfunction "2_2") (pintype "passive"))
    )
    (net (code "60") (name "Net-(IC8B-CTRL)") (class "Default")
      (node (ref "C32") (pin "1") (pinfunction "1_1") (pintype "passive"))
      (node (ref "D18") (pin "C") (pinfunction "C_C") (pintype "passive"))
      (node (ref "IC8") (pin "6") (pinfunction "CTRL_6") (pintype "input"))
      (node (ref "R60") (pin "2") (pinfunction "2_2") (pintype "passive"))
    )
    (net (code "61") (name "Net-(IC8B-IN)") (class "Default")
      (node (ref "IC8") (pin "7") (pinfunction "IN_7") (pintype "input"))
      (node (ref "R61") (pin "2") (pinfunction "2_2") (pintype "passive"))
      (node (ref "R66") (pin "2") (pinfunction "2_2") (pintype "passive"))
    )
    (net (code "62") (name "Net-(IC8C-IN)") (class "Default")
      (node (ref "IC8") (pin "10") (pinfunction "IN_10") (pintype "input"))
      (node (ref "R64") (pin "2") (pinfunction "2_2") (pintype "passive"))
      (node (ref "R67") (pin "2") (pinfunction "2_2") (pintype "passive"))
    )
    (net (code "63") (name "Net-(IC8D-IN)") (class "Default")
      (node (ref "IC8") (pin "15") (pinfunction "IN_15") (pintype "input"))
      (node (ref "R53") (pin "2") (pinfunction "2_2") (pintype "passive"))
      (node (ref "R57") (pin "2") (pinfunction "2_2") (pintype "passive"))
    )
    (net (code "64") (name "Net-(IC9A--IN)") (class "Default")
      (node (ref "IC9") (pin "2") (pinfunction "-IN_2") (pintype "input"))
      (node (ref "R71") (pin "1") (pinfunction "1_1") (pintype "passive"))
      (node (ref "R72") (pin "2") (pinfunction "2_2") (pintype "passive"))
      (node (ref "R73") (pin "1") (pinfunction "1_1") (pintype "passive"))
      (node (ref "R75") (pin "1") (pinfunction "1_1") (pintype "passive"))
    )
    (net (code "65") (name "Net-(IC9C-OUT)") (class "Default")
      (node (ref "C41") (pin "2") (pinfunction "2_2") (pintype "passive"))
      (node (ref "IC9") (pin "8") (pinfunction "OUT_8") (pintype "output"))
      (node (ref "R128") (pin "1") (pinfunction "1_1") (pintype "passive"))
      (node (ref "R71") (pin "2") (pinfunction "2_2") (pintype "passive"))
    )
    (net (code "66") (name "Net-(IC9D-OUT)") (class "Default")
      (node (ref "IC9") (pin "14") (pinfunction "OUT_14") (pintype "output"))
      (node (ref "R73") (pin "2") (pinfunction "2_2") (pintype "passive"))
      (node (ref "R74") (pin "1") (pinfunction "1_1") (pintype "passive"))
      (node (ref "R88") (pin "1") (pinfunction "1_1") (pintype "passive"))
      (node (ref "R99") (pin "1") (pinfunction "1_1") (pintype "passive"))
    )
    (net (code "67") (name "Net-(IC10A--IN)") (class "Default")
      (node (ref "C38") (pin "2") (pinfunction "2_2") (pintype "passive"))
      (node (ref "IC10") (pin "2") (pinfunction "-IN_2") (pintype "input"))
      (node (ref "R69") (pin "P$3") (pinfunction "A_P$3") (pintype "passive"))
      (node (ref "R78") (pin "2") (pinfunction "2_2") (pintype "passive"))
      (node (ref "R79") (pin "2") (pinfunction "2_2") (pintype "passive"))
      (node (ref "R80") (pin "2") (pinfunction "2_2") (pintype "passive"))
      (node (ref "R84") (pin "1") (pinfunction "1_1") (pintype "passive"))
    )
    (net (code "68") (name "Net-(IC10A-OUT)") (class "Default")
      (node (ref "C38") (pin "1") (pinfunction "1_1") (pintype "passive"))
      (node (ref "D10") (pin "C") (pinfunction "C_C") (pintype "passive"))
      (node (ref "IC10") (pin "1") (pinfunction "OUT_1") (pintype "output"))
      (node (ref "IC11") (pin "11") (pinfunction "CTRL_11") (pintype "input"))
      (node (ref "R84") (pin "2") (pinfunction "2_2") (pintype "passive"))
    )
    (net (code "69") (name "Net-(IC10B--IN)") (class "Default")
      (node (ref "IC10") (pin "6") (pinfunction "-IN_6") (pintype "input"))
      (node (ref "R91") (pin "2") (pinfunction "2_2") (pintype "passive"))
      (node (ref "R92") (pin "1") (pinfunction "1_1") (pintype "passive"))
    )
    (net (code "70") (name "Net-(IC10B-OUT)") (class "Default")
      (node (ref "IC10") (pin "7") (pinfunction "OUT_7") (pintype "output"))
      (node (ref "R92") (pin "2") (pinfunction "2_2") (pintype "passive"))
      (node (ref "R95") (pin "1") (pinfunction "1_1") (pintype "passive"))
    )
    (net (code "71") (name "Net-(IC10C--IN)") (class "Default")
      (node (ref "C46") (pin "2") (pinfunction "2_2") (pintype "passive"))
      (node (ref "D12") (pin "A") (pinfunction "A_A") (pintype "passive"))
      (node (ref "IC10") (pin "9") (pinfunction "-IN_9") (pintype "input"))
      (node (ref "R65") (pin "P$1") (pinfunction "E_P$1") (pintype "passive"))
      (node (ref "R93") (pin "1") (pinfunction "1_1") (pintype "passive"))
      (node (ref "R95") (pin "2") (pinfunction "2_2") (pintype "passive"))
    )
    (net (code "72") (name "Net-(IC10C-OUT)") (class "Default")
      (node (ref "D12") (pin "C") (pinfunction "C_C") (pintype "passive"))
      (node (ref "D17") (pin "A") (pinfunction "A_A") (pintype "passive"))
      (node (ref "IC10") (pin "8") (pinfunction "OUT_8") (pintype "output"))
    )
    (net (code "73") (name "Net-(IC10D--IN)") (class "Default")
      (node (ref "C39") (pin "2") (pinfunction "2_2") (pintype "passive"))
      (node (ref "D11") (pin "A") (pinfunction "A_A") (pintype "passive"))
      (node (ref "IC10") (pin "13") (pinfunction "-IN_13") (pintype "input"))
      (node (ref "R68") (pin "P$3") (pinfunction "A_P$3") (pintype "passive"))
      (node (ref "R81") (pin "2") (pinfunction "2_2") (pintype "passive"))
      (node (ref "R82") (pin "2") (pinfunction "2_2") (pintype "passive"))
      (node (ref "R85") (pin "1") (pinfunction "1_1") (pintype "passive"))
    )
    (net (code "74") (name "Net-(IC10D-OUT)") (class "Default")
      (node (ref "D11") (pin "C") (pinfunction "C_C") (pintype "passive"))
      (node (ref "D16") (pin "A") (pinfunction "A_A") (pintype "passive"))
      (node (ref "IC10") (pin "14") (pinfunction "OUT_14") (pintype "output"))
    )
    (net (code "75") (name "Net-(IC11A-CTRL)") (class "Default")
      (node (ref "C39") (pin "1") (pinfunction "1_1") (pintype "passive"))
      (node (ref "D16") (pin "C") (pinfunction "C_C") (pintype "passive"))
      (node (ref "IC11") (pin "14") (pinfunction "CTRL_14") (pintype "input"))
      (node (ref "IC11") (pin "3") (pinfunction "CTRL_3") (pintype "input"))
      (node (ref "R85") (pin "2") (pinfunction "2_2") (pintype "passive"))
    )
    (net (code "76") (name "Net-(IC11A-IN)") (class "Default")
      (node (ref "IC11") (pin "2") (pinfunction "IN_2") (pintype "input"))
      (node (ref "R86") (pin "2") (pinfunction "2_2") (pintype "passive"))
      (node (ref "R89") (pin "2") (pinfunction "2_2") (pintype "passive"))
    )
    (net (code "77") (name "Net-(IC11A-OUT)") (class "Default")
      (node (ref "C40") (pin "1") (pinfunction "1_1") (pintype "passive"))
      (node (ref "IC11") (pin "4") (pinfunction "OUT_4") (pintype "output"))
      (node (ref "IC9") (pin "6") (pinfunction "-IN_6") (pintype "input"))
    )
    (net (code "78") (name "Net-(IC11B-CTRL)") (class "Default")
      (node (ref "C46") (pin "1") (pinfunction "1_1") (pintype "passive"))
      (node (ref "D17") (pin "C") (pinfunction "C_C") (pintype "passive"))
      (node (ref "IC11") (pin "6") (pinfunction "CTRL_6") (pintype "input"))
      (node (ref "R93") (pin "2") (pinfunction "2_2") (pintype "passive"))
    )
    (net (code "79") (name "Net-(IC11B-IN)") (class "Default")
      (node (ref "IC11") (pin "7") (pinfunction "IN_7") (pintype "input"))
      (node (ref "R94") (pin "2") (pinfunction "2_2") (pintype "passive"))
      (node (ref "R98") (pin "2") (pinfunction "2_2") (pintype "passive"))
    )
    (net (code "80") (name "Net-(IC11B-OUT)") (class "Default")
      (node (ref "IC11") (pin "5") (pinfunction "OUT_5") (pintype "output"))
      (node (ref "IC9") (pin "13") (pinfunction "-IN_13") (pintype "input"))
      (node (ref "R76") (pin "2") (pinfunction "2_2") (pintype "passive"))
    )
    (net (code "81") (name "Net-(IC11C-IN)") (class "Default")
      (node (ref "IC11") (pin "10") (pinfunction "IN_10") (pintype "input"))
      (node (ref "R97") (pin "2") (pinfunction "2_2") (pintype "passive"))
      (node (ref "R99") (pin "2") (pinfunction "2_2") (pintype "passive"))
    )
    (net (code "82") (name "Net-(IC11D-IN)") (class "Default")
      (node (ref "IC11") (pin "15") (pinfunction "IN_15") (pintype "input"))
      (node (ref "R87") (pin "2") (pinfunction "2_2") (pintype "passive"))
      (node (ref "R90") (pin "2") (pinfunction "2_2") (pintype "passive"))
    )
    (net (code "83") (name "Net-(IC11D-OUT)") (class "Default")
      (node (ref "C41") (pin "1") (pinfunction "1_1") (pintype "passive"))
      (node (ref "IC11") (pin "13") (pinfunction "OUT_13") (pintype "output"))
      (node (ref "IC9") (pin "9") (pinfunction "-IN_9") (pintype "input"))
    )
    (net (code "84") (name "Net-(IC12A--IN)") (class "Default")
      (node (ref "IC12") (pin "2") (pinfunction "-IN_2") (pintype "input"))
      (node (ref "R102") (pin "1") (pinfunction "1_1") (pintype "passive"))
      (node (ref "R105") (pin "2") (pinfunction "2_2") (pintype "passive"))
    )
    (net (code "85") (name "Net-(IC12A-OUT)") (class "Default")
      (node (ref "IC12") (pin "1") (pinfunction "OUT_1") (pintype "output"))
      (node (ref "R102") (pin "2") (pinfunction "2_2") (pintype "passive"))
      (node (ref "R106") (pin "1") (pinfunction "1_1") (pintype "passive"))
    )
    (net (code "86") (name "Net-(IC12B--IN)") (class "Default")
      (node (ref "IC12") (pin "6") (pinfunction "-IN_6") (pintype "input"))
      (node (ref "R103") (pin "1") (pinfunction "1_1") (pintype "passive"))
      (node (ref "R106") (pin "2") (pinfunction "2_2") (pintype "passive"))
      (node (ref "R122") (pin "1") (pinfunction "1_1") (pintype "passive"))
    )
    (net (code "87") (name "Net-(IC13B-OUT)") (class "Default")
      (node (ref "IC13") (pin "7") (pinfunction "OUT_7") (pintype "output"))
      (node (ref "R104") (pin "1") (pinfunction "1_1") (pintype "passive"))
      (node (ref "R110") (pin "2") (pinfunction "2_2") (pintype "passive"))
    )
    (net (code "88") (name "Net-(IC14A-+IN)") (class "Default")
      (node (ref "IC14") (pin "3") (pinfunction "+IN_3") (pintype "input"))
      (node (ref "IC14") (pin "6") (pinfunction "-IN_6") (pintype "input"))
      (node (ref "R115") (pin "2") (pinfunction "2_2") (pintype "passive"))
      (node (ref "R117") (pin "2") (pinfunction "2_2") (pintype "passive"))
      (node (ref "R118") (pin "1") (pinfunction "1_1") (pintype "passive"))
    )
    (net (code "89") (name "Net-(IC14A--IN)") (class "Default")
      (node (ref "IC14") (pin "2") (pinfunction "-IN_2") (pintype "input"))
      (node (ref "R119") (pin "2") (pinfunction "2_2") (pintype "passive"))
      (node (ref "R121") (pin "1") (pinfunction "1_1") (pintype "passive"))
    )
    (net (code "90") (name "Net-(IC14A-OUT)") (class "Default")
      (node (ref "D13") (pin "A") (pinfunction "A_A") (pintype "passive"))
      (node (ref "IC14") (pin "1") (pinfunction "OUT_1") (pintype "output"))
    )
    (net (code "91") (name "Net-(IC14B-+IN)") (class "Default")
      (node (ref "IC14") (pin "5") (pinfunction "+IN_5") (pintype "input"))
      (node (ref "R119") (pin "1") (pinfunction "1_1") (pintype "passive"))
      (node (ref "R120") (pin "2") (pinfunction "2_2") (pintype "passive"))
    )
    (net (code "92") (name "Net-(IC14B-OUT)") (class "Default")
      (node (ref "D14") (pin "A") (pinfunction "A_A") (pintype "passive"))
      (node (ref "IC14") (pin "7") (pinfunction "OUT_7") (pintype "output"))
    )
    (net (code "93") (name "Net-(J1-3)") (class "Default")
      (node (ref "J1") (pin "P3") (pinfunction "3_P3") (pintype "passive"))
      (node (ref "R6") (pin "1") (pinfunction "1_1") (pintype "passive"))
    )
    (net (code "94") (name "Net-(J2-3)") (class "Default")
      (node (ref "J2") (pin "P3") (pinfunction "3_P3") (pintype "passive"))
      (node (ref "R30") (pin "1") (pinfunction "1_1") (pintype "passive"))
    )
    (net (code "95") (name "Net-(J3-3)") (class "Default")
      (node (ref "J3") (pin "P3") (pinfunction "3_P3") (pintype "passive"))
      (node (ref "R48") (pin "1") (pinfunction "1_1") (pintype "passive"))
    )
    (net (code "96") (name "Net-(J4-3)") (class "Default")
      (node (ref "J4") (pin "P3") (pinfunction "3_P3") (pintype "passive"))
      (node (ref "R45") (pin "1") (pinfunction "1_1") (pintype "passive"))
    )
    (net (code "97") (name "Net-(J5-3)") (class "Default")
      (node (ref "J5") (pin "P3") (pinfunction "3_P3") (pintype "passive"))
      (node (ref "R58") (pin "1") (pinfunction "1_1") (pintype "passive"))
    )
    (net (code "98") (name "Net-(J6-3)") (class "Default")
      (node (ref "J6") (pin "P3") (pinfunction "3_P3") (pintype "passive"))
      (node (ref "R91") (pin "1") (pinfunction "1_1") (pintype "passive"))
    )
    (net (code "99") (name "Net-(J7-3)") (class "Default")
      (node (ref "J7") (pin "P3") (pinfunction "3_P3") (pintype "passive"))
      (node (ref "R82") (pin "1") (pinfunction "1_1") (pintype "passive"))
    )
    (net (code "100") (name "Net-(J8-3)") (class "Default")
      (node (ref "J8") (pin "P3") (pinfunction "3_P3") (pintype "passive"))
      (node (ref "R78") (pin "1") (pinfunction "1_1") (pintype "passive"))
    )
    (net (code "101") (name "Net-(J9-3)") (class "Default")
      (node (ref "J9") (pin "P3") (pinfunction "3_P3") (pintype "passive"))
      (node (ref "R9") (pin "1") (pinfunction "1_1") (pintype "passive"))
    )
    (net (code "102") (name "Net-(J10-3)") (class "Default")
      (node (ref "J10") (pin "P3") (pinfunction "3_P3") (pintype "passive"))
      (node (ref "R27") (pin "1") (pinfunction "1_1") (pintype "passive"))
    )
    (net (code "103") (name "Net-(J13-3)") (class "Default")
      (node (ref "J13") (pin "P3") (pinfunction "3_P3") (pintype "passive"))
      (node (ref "R105") (pin "1") (pinfunction "1_1") (pintype "passive"))
    )
    (net (code "104") (name "Net-(J14-3)") (class "Default")
      (node (ref "J14") (pin "P3") (pinfunction "3_P3") (pintype "passive"))
      (node (ref "R111") (pin "2") (pinfunction "2_2") (pintype "passive"))
    )
    (net (code "105") (name "Net-(J15-3)") (class "Default")
      (node (ref "J15") (pin "P3") (pinfunction "3_P3") (pintype "passive"))
      (node (ref "R123") (pin "2") (pinfunction "2_2") (pintype "passive"))
    )
    (net (code "106") (name "Net-(J16-3)") (class "Default")
      (node (ref "J16") (pin "P3") (pinfunction "3_P3") (pintype "passive"))
      (node (ref "R124") (pin "2") (pinfunction "2_2") (pintype "passive"))
    )
    (net (code "107") (name "Net-(J17-3)") (class "Default")
      (node (ref "J17") (pin "P3") (pinfunction "3_P3") (pintype "passive"))
      (node (ref "R125") (pin "2") (pinfunction "2_2") (pintype "passive"))
    )
    (net (code "108") (name "Net-(J18-3)") (class "Default")
      (node (ref "J18") (pin "P3") (pinfunction "3_P3") (pintype "passive"))
      (node (ref "R126") (pin "2") (pinfunction "2_2") (pintype "passive"))
    )
    (net (code "109") (name "Net-(J19-3)") (class "Default")
      (node (ref "J19") (pin "P3") (pinfunction "3_P3") (pintype "passive"))
      (node (ref "R127") (pin "2") (pinfunction "2_2") (pintype "passive"))
    )
    (net (code "110") (name "Net-(J20-3)") (class "Default")
      (node (ref "J20") (pin "P3") (pinfunction "3_P3") (pintype "passive"))
      (node (ref "R128") (pin "2") (pinfunction "2_2") (pintype "passive"))
    )
    (net (code "111") (name "Net-(JP5-Pad2)") (class "Default")
      (node (ref "JP5") (pin "2") (pinfunction "2_2") (pintype "passive"))
      (node (ref "R122") (pin "2") (pinfunction "2_2") (pintype "passive"))
    )
    (net (code "112") (name "Net-(JP11-Pad10)") (class "Default")
      (node (ref "JP11") (pin "10") (pinfunction "10_10") (pintype "passive"))
      (node (ref "JP11") (pin "9") (pinfunction "9_9") (pintype "passive"))
      (node (ref "P1") (pin "2") (pinfunction "2_2") (pintype "bidirectional"))
    )
    (net (code "113") (name "Net-(LED1-C)") (class "Default")
      (node (ref "LED1") (pin "K") (pinfunction "C_K") (pintype "passive"))
      (node (ref "Q1") (pin "C") (pinfunction "C_C") (pintype "passive"))
    )
    (net (code "114") (name "Net-(LED1-PadA)") (class "Default")
      (node (ref "LED1") (pin "A") (pinfunction "A_A") (pintype "passive"))
      (node (ref "R112") (pin "1") (pinfunction "1_1") (pintype "passive"))
    )
    (net (code "115") (name "Net-(Q1-PadB)") (class "Default")
      (node (ref "Q1") (pin "B") (pinfunction "B_B") (pintype "passive"))
      (node (ref "R114") (pin "2") (pinfunction "2_2") (pintype "passive"))
      (node (ref "R116") (pin "2") (pinfunction "2_2") (pintype "passive"))
    )
    (net (code "116") (name "Net-(R3-S)") (class "Default")
      (node (ref "R3") (pin "P$2") (pinfunction "S_P$2") (pintype "passive"))
      (node (ref "R5") (pin "2") (pinfunction "2_2") (pintype "passive"))
    )
    (net (code "117") (name "Net-(R4-S)") (class "Default")
      (node (ref "R12") (pin "2") (pinfunction "2_2") (pintype "passive"))
      (node (ref "R4") (pin "P$2") (pinfunction "S_P$2") (pintype "passive"))
    )
    (net (code "118") (name "Net-(R34-S)") (class "Default")
      (node (ref "R34") (pin "P$2") (pinfunction "S_P$2") (pintype "passive"))
      (node (ref "R43") (pin "2") (pinfunction "2_2") (pintype "passive"))
    )
    (net (code "119") (name "Net-(R36-S)") (class "Default")
      (node (ref "R36") (pin "P$2") (pinfunction "S_P$2") (pintype "passive"))
      (node (ref "R49") (pin "2") (pinfunction "2_2") (pintype "passive"))
    )
    (net (code "120") (name "Net-(R39-Pad2)") (class "Default")
      (node (ref "R39") (pin "2") (pinfunction "2_2") (pintype "passive"))
      (node (ref "R41") (pin "1") (pinfunction "1_1") (pintype "passive"))
    )
    (net (code "121") (name "Net-(R42-S)") (class "Default")
      (node (ref "R42") (pin "P$2") (pinfunction "S_P$2") (pintype "passive"))
      (node (ref "R54") (pin "2") (pinfunction "2_2") (pintype "passive"))
    )
    (net (code "122") (name "Net-(R65-S)") (class "Default")
      (node (ref "R65") (pin "P$2") (pinfunction "S_P$2") (pintype "passive"))
      (node (ref "R70") (pin "2") (pinfunction "2_2") (pintype "passive"))
    )
    (net (code "123") (name "Net-(R68-S)") (class "Default")
      (node (ref "R68") (pin "P$2") (pinfunction "S_P$2") (pintype "passive"))
      (node (ref "R77") (pin "2") (pinfunction "2_2") (pintype "passive"))
    )
    (net (code "124") (name "Net-(R69-S)") (class "Default")
      (node (ref "R69") (pin "P$2") (pinfunction "S_P$2") (pintype "passive"))
      (node (ref "R83") (pin "2") (pinfunction "2_2") (pintype "passive"))
    )
    (net (code "125") (name "Net-(R74-Pad2)") (class "Default")
      (node (ref "R74") (pin "2") (pinfunction "2_2") (pintype "passive"))
      (node (ref "R76") (pin "1") (pinfunction "1_1") (pintype "passive"))
    )
    (net (code "126") (name "Net-(R100-S)") (class "Default")
      (node (ref "R100") (pin "P$2") (pinfunction "S_P$2") (pintype "passive"))
      (node (ref "R109") (pin "2") (pinfunction "2_2") (pintype "passive"))
    )
    (net (code "127") (name "Net-(R101-S)") (class "Default")
      (node (ref "R101") (pin "P$2") (pinfunction "S_P$2") (pintype "passive"))
      (node (ref "R108") (pin "2") (pinfunction "2_2") (pintype "passive"))
    )
    (net (code "128") (name "OUTPUT") (class "Default")
      (node (ref "C57") (pin "2") (pinfunction "2_2") (pintype "passive"))
      (node (ref "IC13") (pin "1") (pinfunction "OUT_1") (pintype "output"))
      (node (ref "R107") (pin "2") (pinfunction "2_2") (pintype "passive"))
      (node (ref "R111") (pin "1") (pinfunction "1_1") (pintype "passive"))
    )
    (net (code "129") (name "PLUS_BUS") (class "Default")
      (node (ref "IC13") (pin "6") (pinfunction "-IN_6") (pintype "input"))
      (node (ref "IC5") (pin "12") (pinfunction "OUT_12") (pintype "output"))
      (node (ref "R110") (pin "1") (pinfunction "1_1") (pintype "passive"))
      (node (ref "R33") (pin "2") (pinfunction "2_2") (pintype "passive"))
      (node (ref "R55") (pin "2") (pinfunction "2_2") (pintype "passive"))
      (node (ref "R88") (pin "2") (pinfunction "2_2") (pintype "passive"))
    )
    (net (code "130") (name "VCC") (class "Default")
      (node (ref "C1") (pin "+") (pinfunction "+_+") (pintype "passive"))
      (node (ref "C12") (pin "1") (pinfunction "1_1") (pintype "passive"))
      (node (ref "C21") (pin "1") (pinfunction "1_1") (pintype "passive"))
      (node (ref "C27") (pin "1") (pinfunction "1_1") (pintype "passive"))
      (node (ref "C31") (pin "1") (pinfunction "1_1") (pintype "passive"))
      (node (ref "C36") (pin "1") (pinfunction "1_1") (pintype "passive"))
      (node (ref "C42") (pin "1") (pinfunction "1_1") (pintype "passive"))
      (node (ref "C43") (pin "1") (pinfunction "1_1") (pintype "passive"))
      (node (ref "C5") (pin "1") (pinfunction "1_1") (pintype "passive"))
      (node (ref "C50") (pin "1") (pinfunction "1_1") (pintype "passive"))
      (node (ref "C52") (pin "1") (pinfunction "1_1") (pintype "passive"))
      (node (ref "C56") (pin "1") (pinfunction "1_1") (pintype "passive"))
      (node (ref "C58") (pin "+") (pinfunction "+_+") (pintype "passive"))
      (node (ref "C9") (pin "1") (pinfunction "1_1") (pintype "passive"))
      (node (ref "D2") (pin "C") (pinfunction "C_C") (pintype "passive"))
      (node (ref "IC10") (pin "4") (pinfunction "V+_4") (pintype "power_in"))
      (node (ref "IC11") (pin "16") (pinfunction "V+_16") (pintype "power_in"))
      (node (ref "IC12") (pin "8") (pinfunction "V+_8") (pintype "power_in"))
      (node (ref "IC13") (pin "8") (pinfunction "V+_8") (pintype "power_in"))
      (node (ref "IC14") (pin "8") (pinfunction "V+_8") (pintype "power_in"))
      (node (ref "IC3") (pin "8") (pinfunction "V+_8") (pintype "power_in"))
      (node (ref "IC4") (pin "4") (pinfunction "V+_4") (pintype "power_in"))
      (node (ref "IC5") (pin "16") (pinfunction "V+_16") (pintype "power_in"))
      (node (ref "IC6") (pin "4") (pinfunction "V+_4") (pintype "power_in"))
      (node (ref "IC7") (pin "4") (pinfunction "V+_4") (pintype "power_in"))
      (node (ref "IC8") (pin "16") (pinfunction "V+_16") (pintype "power_in"))
      (node (ref "IC9") (pin "4") (pinfunction "V+_4") (pintype "power_in"))
      (node (ref "R1") (pin "1") (pinfunction "1_1") (pintype "passive"))
      (node (ref "R112") (pin "2") (pinfunction "2_2") (pintype "passive"))
    )
    (net (code "131") (name "VEE") (class "Default")
      (node (ref "C13") (pin "2") (pinfunction "2_2") (pintype "passive"))
      (node (ref "C2") (pin "-") (pinfunction "-_-") (pintype "passive"))
      (node (ref "C20") (pin "2") (pinfunction "2_2") (pintype "passive"))
      (node (ref "C22") (pin "2") (pinfunction "2_2") (pintype "passive"))
      (node (ref "C28") (pin "2") (pinfunction "2_2") (pintype "passive"))
      (node (ref "C35") (pin "2") (pinfunction "2_2") (pintype "passive"))
      (node (ref "C37") (pin "2") (pinfunction "2_2") (pintype "passive"))
      (node (ref "C44") (pin "2") (pinfunction "2_2") (pintype "passive"))
      (node (ref "C51") (pin "2") (pinfunction "2_2") (pintype "passive"))
      (node (ref "C53") (pin "2") (pinfunction "2_2") (pintype "passive"))
      (node (ref "C54") (pin "2") (pinfunction "2_2") (pintype "passive"))
      (node (ref "C8") (pin "2") (pinfunction "2_2") (pintype "passive"))
      (node (ref "D1") (pin "A") (pinfunction "A_A") (pintype "passive"))
      (node (ref "IC10") (pin "11") (pinfunction "V-_11") (pintype "power_in"))
      (node (ref "IC11") (pin "9") (pinfunction "V-_9") (pintype "power_in"))
      (node (ref "IC12") (pin "4") (pinfunction "V-_4") (pintype "power_in"))
      (node (ref "IC13") (pin "4") (pinfunction "V-_4") (pintype "power_in"))
      (node (ref "IC3") (pin "4") (pinfunction "V-_4") (pintype "power_in"))
      (node (ref "IC4") (pin "11") (pinfunction "V-_11") (pintype "power_in"))
      (node (ref "IC5") (pin "9") (pinfunction "V-_9") (pintype "power_in"))
      (node (ref "IC6") (pin "11") (pinfunction "V-_11") (pintype "power_in"))
      (node (ref "IC7") (pin "11") (pinfunction "V-_11") (pintype "power_in"))
      (node (ref "IC8") (pin "9") (pinfunction "V-_9") (pintype "power_in"))
      (node (ref "IC9") (pin "11") (pinfunction "V-_11") (pintype "power_in"))
      (node (ref "P1") (pin "1") (pinfunction "1_1") (pintype "bidirectional"))
      (node (ref "R2") (pin "1") (pinfunction "1_1") (pintype "passive"))
    )
    (net (code "132") (name "unconnected-(IC5E-MODE-Pad1)") (class "Default")
      (node (ref "IC5") (pin "1") (pinfunction "MODE_1") (pintype "input"))
    )
    (net (code "133") (name "unconnected-(IC8E-MODE-Pad1)") (class "Default")
      (node (ref "IC8") (pin "1") (pinfunction "MODE_1") (pintype "input"))
    )
    (net (code "134") (name "unconnected-(IC11E-MODE-Pad1)") (class "Default")
      (node (ref "IC11") (pin "1") (pinfunction "MODE_1") (pintype "input"))
    )
    (net (code "135") (name "unconnected-(J1-2-PadP2)") (class "Default")
      (node (ref "J1") (pin "P2") (pinfunction "2_P2") (pintype "passive"))
    )
    (net (code "136") (name "unconnected-(J2-2-PadP2)") (class "Default")
      (node (ref "J2") (pin "P2") (pinfunction "2_P2") (pintype "passive"))
    )
    (net (code "137") (name "unconnected-(J3-2-PadP2)") (class "Default")
      (node (ref "J3") (pin "P2") (pinfunction "2_P2") (pintype "passive"))
    )
    (net (code "138") (name "unconnected-(J4-2-PadP2)") (class "Default")
      (node (ref "J4") (pin "P2") (pinfunction "2_P2") (pintype "passive"))
    )
    (net (code "139") (name "unconnected-(J5-2-PadP2)") (class "Default")
      (node (ref "J5") (pin "P2") (pinfunction "2_P2") (pintype "passive"))
    )
    (net (code "140") (name "unconnected-(J6-2-PadP2)") (class "Default")
      (node (ref "J6") (pin "P2") (pinfunction "2_P2") (pintype "passive"))
    )
    (net (code "141") (name "unconnected-(J7-2-PadP2)") (class "Default")
      (node (ref "J7") (pin "P2") (pinfunction "2_P2") (pintype "passive"))
    )
    (net (code "142") (name "unconnected-(J8-2-PadP2)") (class "Default")
      (node (ref "J8") (pin "P2") (pinfunction "2_P2") (pintype "passive"))
    )
    (net (code "143") (name "unconnected-(J9-2-PadP2)") (class "Default")
      (node (ref "J9") (pin "P2") (pinfunction "2_P2") (pintype "passive"))
    )
    (net (code "144") (name "unconnected-(J10-2-PadP2)") (class "Default")
      (node (ref "J10") (pin "P2") (pinfunction "2_P2") (pintype "passive"))
    )
    (net (code "145") (name "unconnected-(J11-2-PadP2)") (class "Default")
      (node (ref "J11") (pin "P2") (pinfunction "2_P2") (pintype "passive"))
    )
    (net (code "146") (name "unconnected-(J12-2-PadP2)") (class "Default")
      (node (ref "J12") (pin "P2") (pinfunction "2_P2") (pintype "passive"))
    )
    (net (code "147") (name "unconnected-(J13-2-PadP2)") (class "Default")
      (node (ref "J13") (pin "P2") (pinfunction "2_P2") (pintype "passive"))
    )
    (net (code "148") (name "unconnected-(J14-2-PadP2)") (class "Default")
      (node (ref "J14") (pin "P2") (pinfunction "2_P2") (pintype "passive"))
    )
    (net (code "149") (name "unconnected-(J15-2-PadP2)") (class "Default")
      (node (ref "J15") (pin "P2") (pinfunction "2_P2") (pintype "passive"))
    )
    (net (code "150") (name "unconnected-(J16-2-PadP2)") (class "Default")
      (node (ref "J16") (pin "P2") (pinfunction "2_P2") (pintype "passive"))
    )
    (net (code "151") (name "unconnected-(J17-2-PadP2)") (class "Default")
      (node (ref "J17") (pin "P2") (pinfunction "2_P2") (pintype "passive"))
    )
    (net (code "152") (name "unconnected-(J18-2-PadP2)") (class "Default")
      (node (ref "J18") (pin "P2") (pinfunction "2_P2") (pintype "passive"))
    )
    (net (code "153") (name "unconnected-(J19-2-PadP2)") (class "Default")
      (node (ref "J19") (pin "P2") (pinfunction "2_P2") (pintype "passive"))
    )
    (net (code "154") (name "unconnected-(J20-2-PadP2)") (class "Default")
      (node (ref "J20") (pin "P2") (pinfunction "2_P2") (pintype "passive"))
    )
    (net (code "155") (name "unconnected-(JP5-Pad1)") (class "Default")
      (node (ref "JP5") (pin "1") (pinfunction "1_1") (pintype "passive"))
    )
  )
)
